# Facec.net
KiCad netlist of a schematic drawn in EAGLE
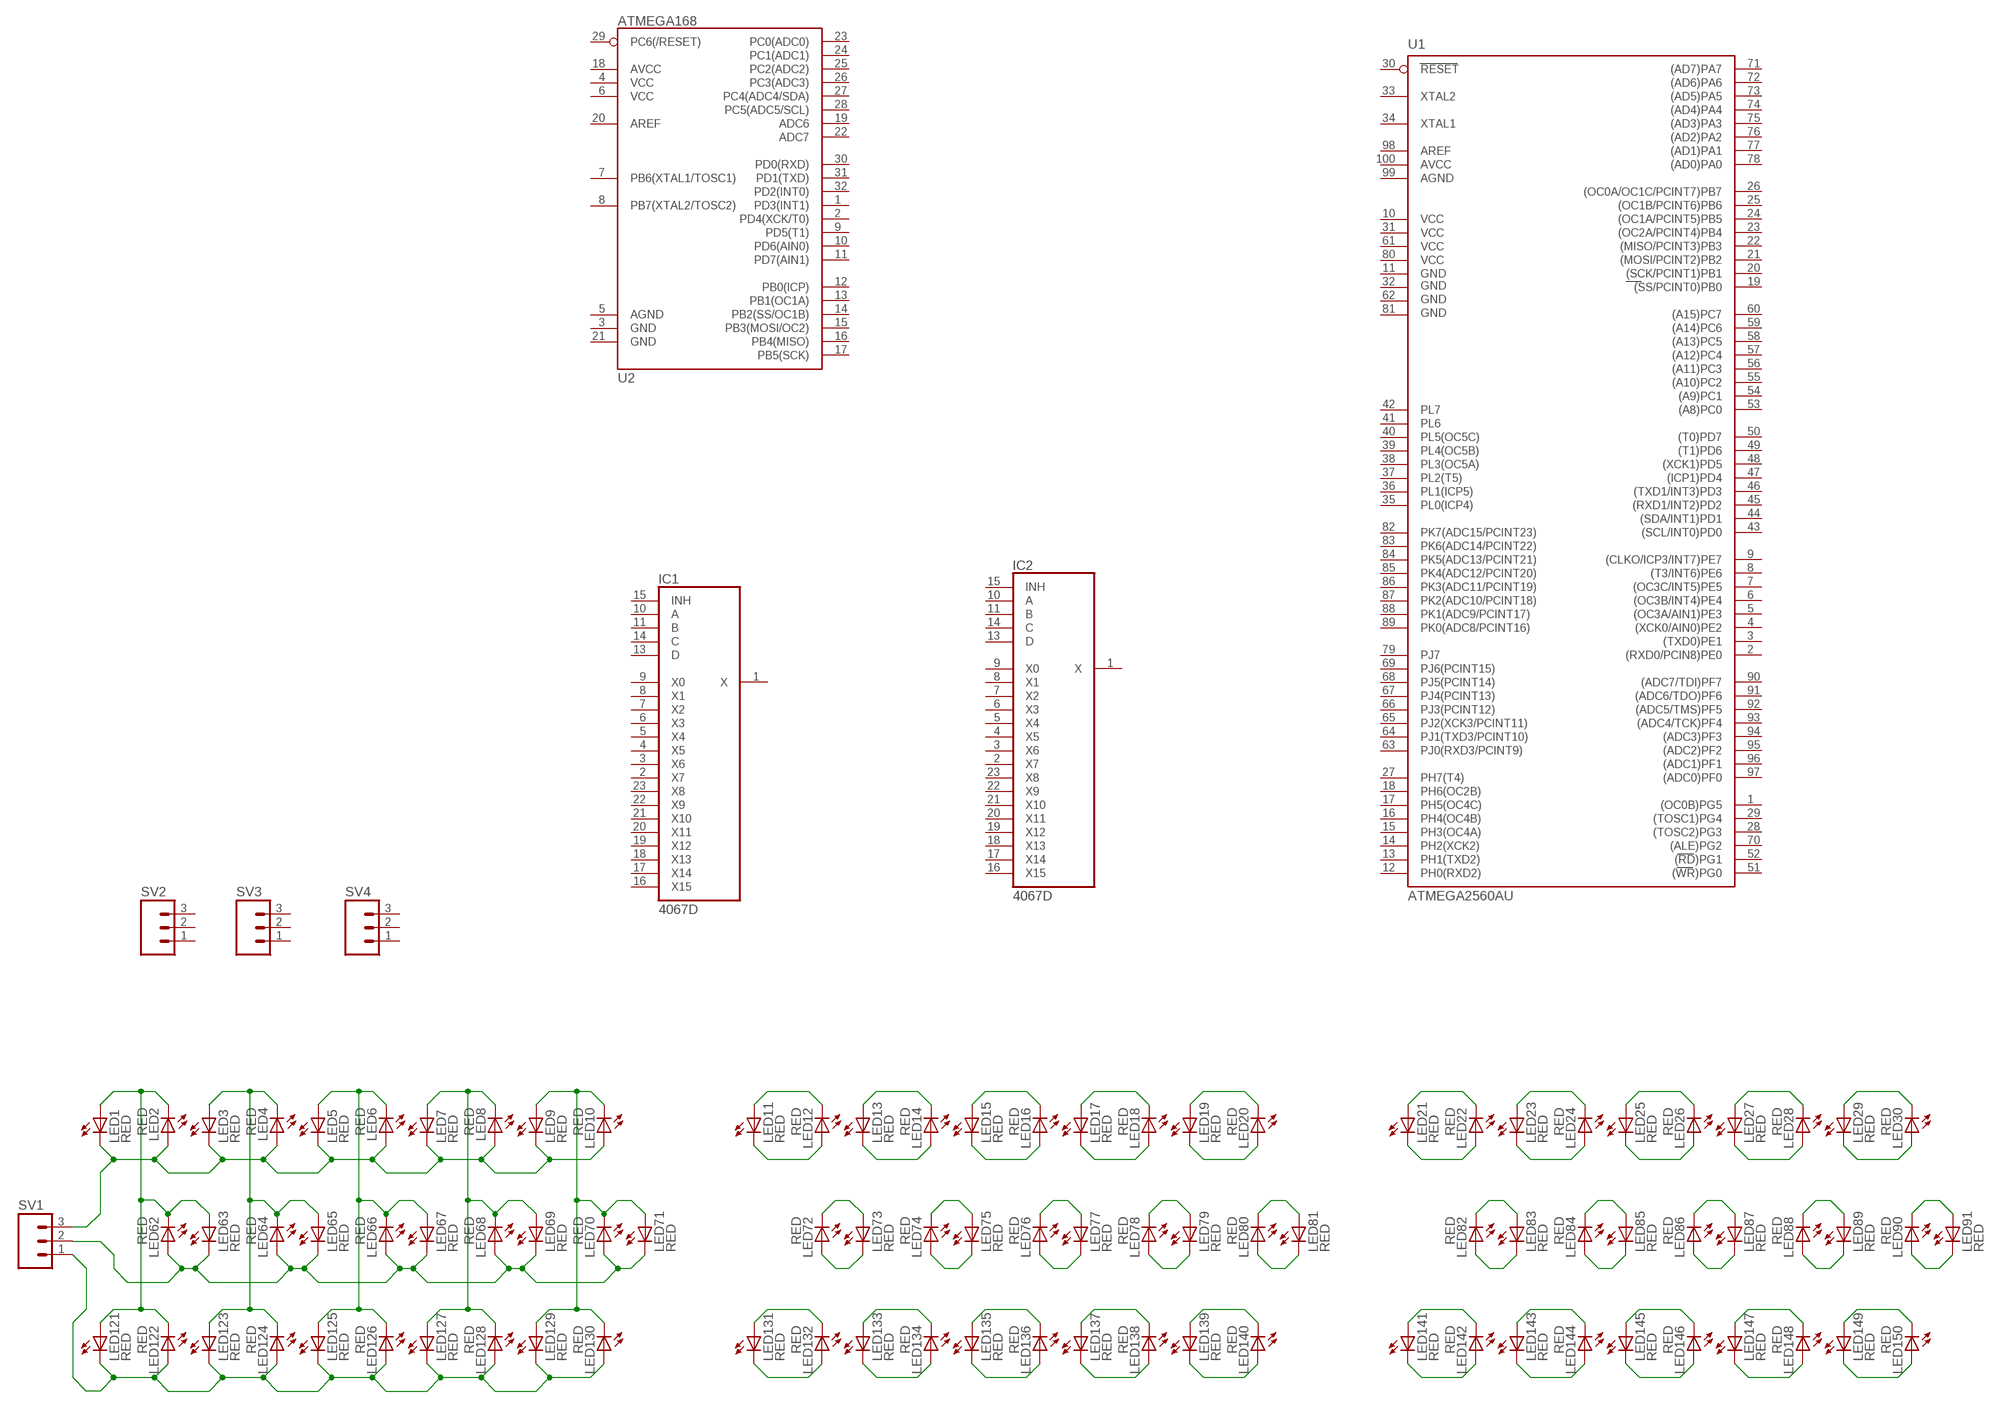
[diagram p0: schematic, sheet 1, part 1 of 2]
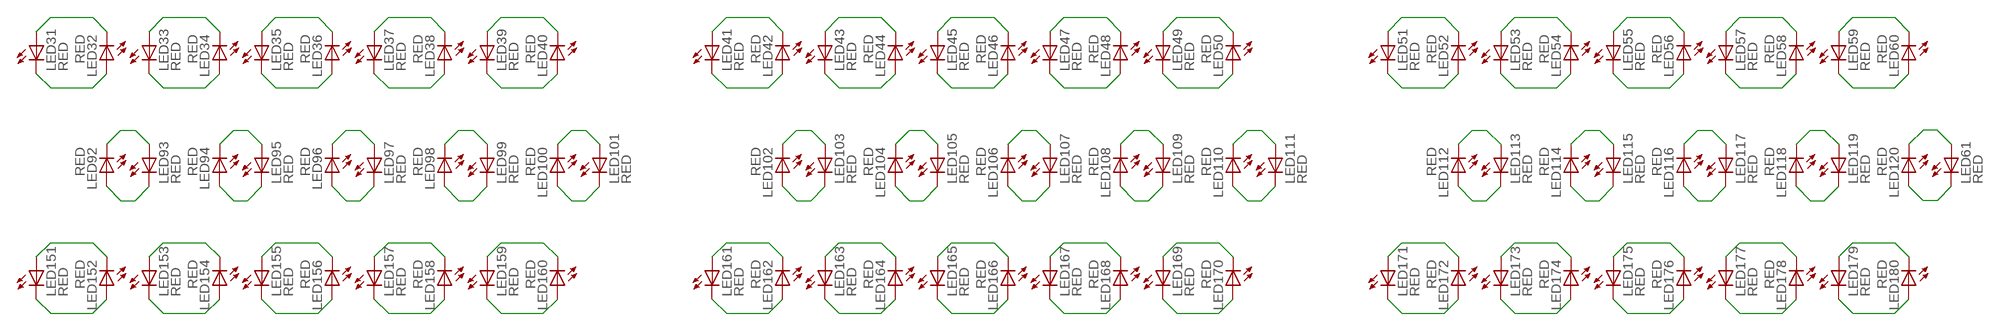
[diagram p1: schematic, sheet 1, part 2 of 2]

(export (version "E")
  (design (tool "Eeschema 10.0.6"))
  (components
    (comp (ref "IC1")
      (value "4067D")
      (footprint "eagle-import:SO24W")
      (libsource (lib "eagle-import") (part "4067D"))
    )
    (comp (ref "IC2")
      (value "4067D")
      (footprint "eagle-import:SO24W")
      (libsource (lib "eagle-import") (part "4067D"))
    )
    (comp (ref "LED1")
      (value "RED")
      (footprint "eagle-import:LED-0603")
      (libsource (lib "eagle-import") (part "LED0603"))
    )
    (comp (ref "LED2")
      (value "RED")
      (footprint "eagle-import:LED-0603")
      (libsource (lib "eagle-import") (part "LED0603"))
    )
    (comp (ref "LED3")
      (value "RED")
      (footprint "eagle-import:LED-0603")
      (libsource (lib "eagle-import") (part "LED0603"))
    )
    (comp (ref "LED4")
      (value "RED")
      (footprint "eagle-import:LED-0603")
      (libsource (lib "eagle-import") (part "LED0603"))
    )
    (comp (ref "LED5")
      (value "RED")
      (footprint "eagle-import:LED-0603")
      (libsource (lib "eagle-import") (part "LED0603"))
    )
    (comp (ref "LED6")
      (value "RED")
      (footprint "eagle-import:LED-0603")
      (libsource (lib "eagle-import") (part "LED0603"))
    )
    (comp (ref "LED7")
      (value "RED")
      (footprint "eagle-import:LED-0603")
      (libsource (lib "eagle-import") (part "LED0603"))
    )
    (comp (ref "LED8")
      (value "RED")
      (footprint "eagle-import:LED-0603")
      (libsource (lib "eagle-import") (part "LED0603"))
    )
    (comp (ref "LED9")
      (value "RED")
      (footprint "eagle-import:LED-0603")
      (libsource (lib "eagle-import") (part "LED0603"))
    )
    (comp (ref "LED10")
      (value "RED")
      (footprint "eagle-import:LED-0603")
      (libsource (lib "eagle-import") (part "LED0603"))
    )
    (comp (ref "LED11")
      (value "RED")
      (footprint "eagle-import:LED-0603")
      (libsource (lib "eagle-import") (part "LED0603"))
    )
    (comp (ref "LED12")
      (value "RED")
      (footprint "eagle-import:LED-0603")
      (libsource (lib "eagle-import") (part "LED0603"))
    )
    (comp (ref "LED13")
      (value "RED")
      (footprint "eagle-import:LED-0603")
      (libsource (lib "eagle-import") (part "LED0603"))
    )
    (comp (ref "LED14")
      (value "RED")
      (footprint "eagle-import:LED-0603")
      (libsource (lib "eagle-import") (part "LED0603"))
    )
    (comp (ref "LED15")
      (value "RED")
      (footprint "eagle-import:LED-0603")
      (libsource (lib "eagle-import") (part "LED0603"))
    )
    (comp (ref "LED16")
      (value "RED")
      (footprint "eagle-import:LED-0603")
      (libsource (lib "eagle-import") (part "LED0603"))
    )
    (comp (ref "LED17")
      (value "RED")
      (footprint "eagle-import:LED-0603")
      (libsource (lib "eagle-import") (part "LED0603"))
    )
    (comp (ref "LED18")
      (value "RED")
      (footprint "eagle-import:LED-0603")
      (libsource (lib "eagle-import") (part "LED0603"))
    )
    (comp (ref "LED19")
      (value "RED")
      (footprint "eagle-import:LED-0603")
      (libsource (lib "eagle-import") (part "LED0603"))
    )
    (comp (ref "LED20")
      (value "RED")
      (footprint "eagle-import:LED-0603")
      (libsource (lib "eagle-import") (part "LED0603"))
    )
    (comp (ref "LED21")
      (value "RED")
      (footprint "eagle-import:LED-0603")
      (libsource (lib "eagle-import") (part "LED0603"))
    )
    (comp (ref "LED22")
      (value "RED")
      (footprint "eagle-import:LED-0603")
      (libsource (lib "eagle-import") (part "LED0603"))
    )
    (comp (ref "LED23")
      (value "RED")
      (footprint "eagle-import:LED-0603")
      (libsource (lib "eagle-import") (part "LED0603"))
    )
    (comp (ref "LED24")
      (value "RED")
      (footprint "eagle-import:LED-0603")
      (libsource (lib "eagle-import") (part "LED0603"))
    )
    (comp (ref "LED25")
      (value "RED")
      (footprint "eagle-import:LED-0603")
      (libsource (lib "eagle-import") (part "LED0603"))
    )
    (comp (ref "LED26")
      (value "RED")
      (footprint "eagle-import:LED-0603")
      (libsource (lib "eagle-import") (part "LED0603"))
    )
    (comp (ref "LED27")
      (value "RED")
      (footprint "eagle-import:LED-0603")
      (libsource (lib "eagle-import") (part "LED0603"))
    )
    (comp (ref "LED28")
      (value "RED")
      (footprint "eagle-import:LED-0603")
      (libsource (lib "eagle-import") (part "LED0603"))
    )
    (comp (ref "LED29")
      (value "RED")
      (footprint "eagle-import:LED-0603")
      (libsource (lib "eagle-import") (part "LED0603"))
    )
    (comp (ref "LED30")
      (value "RED")
      (footprint "eagle-import:LED-0603")
      (libsource (lib "eagle-import") (part "LED0603"))
    )
    (comp (ref "LED31")
      (value "RED")
      (footprint "eagle-import:LED-0603")
      (libsource (lib "eagle-import") (part "LED0603"))
    )
    (comp (ref "LED32")
      (value "RED")
      (footprint "eagle-import:LED-0603")
      (libsource (lib "eagle-import") (part "LED0603"))
    )
    (comp (ref "LED33")
      (value "RED")
      (footprint "eagle-import:LED-0603")
      (libsource (lib "eagle-import") (part "LED0603"))
    )
    (comp (ref "LED34")
      (value "RED")
      (footprint "eagle-import:LED-0603")
      (libsource (lib "eagle-import") (part "LED0603"))
    )
    (comp (ref "LED35")
      (value "RED")
      (footprint "eagle-import:LED-0603")
      (libsource (lib "eagle-import") (part "LED0603"))
    )
    (comp (ref "LED36")
      (value "RED")
      (footprint "eagle-import:LED-0603")
      (libsource (lib "eagle-import") (part "LED0603"))
    )
    (comp (ref "LED37")
      (value "RED")
      (footprint "eagle-import:LED-0603")
      (libsource (lib "eagle-import") (part "LED0603"))
    )
    (comp (ref "LED38")
      (value "RED")
      (footprint "eagle-import:LED-0603")
      (libsource (lib "eagle-import") (part "LED0603"))
    )
    (comp (ref "LED39")
      (value "RED")
      (footprint "eagle-import:LED-0603")
      (libsource (lib "eagle-import") (part "LED0603"))
    )
    (comp (ref "LED40")
      (value "RED")
      (footprint "eagle-import:LED-0603")
      (libsource (lib "eagle-import") (part "LED0603"))
    )
    (comp (ref "LED41")
      (value "RED")
      (footprint "eagle-import:LED-0603")
      (libsource (lib "eagle-import") (part "LED0603"))
    )
    (comp (ref "LED42")
      (value "RED")
      (footprint "eagle-import:LED-0603")
      (libsource (lib "eagle-import") (part "LED0603"))
    )
    (comp (ref "LED43")
      (value "RED")
      (footprint "eagle-import:LED-0603")
      (libsource (lib "eagle-import") (part "LED0603"))
    )
    (comp (ref "LED44")
      (value "RED")
      (footprint "eagle-import:LED-0603")
      (libsource (lib "eagle-import") (part "LED0603"))
    )
    (comp (ref "LED45")
      (value "RED")
      (footprint "eagle-import:LED-0603")
      (libsource (lib "eagle-import") (part "LED0603"))
    )
    (comp (ref "LED46")
      (value "RED")
      (footprint "eagle-import:LED-0603")
      (libsource (lib "eagle-import") (part "LED0603"))
    )
    (comp (ref "LED47")
      (value "RED")
      (footprint "eagle-import:LED-0603")
      (libsource (lib "eagle-import") (part "LED0603"))
    )
    (comp (ref "LED48")
      (value "RED")
      (footprint "eagle-import:LED-0603")
      (libsource (lib "eagle-import") (part "LED0603"))
    )
    (comp (ref "LED49")
      (value "RED")
      (footprint "eagle-import:LED-0603")
      (libsource (lib "eagle-import") (part "LED0603"))
    )
    (comp (ref "LED50")
      (value "RED")
      (footprint "eagle-import:LED-0603")
      (libsource (lib "eagle-import") (part "LED0603"))
    )
    (comp (ref "LED51")
      (value "RED")
      (footprint "eagle-import:LED-0603")
      (libsource (lib "eagle-import") (part "LED0603"))
    )
    (comp (ref "LED52")
      (value "RED")
      (footprint "eagle-import:LED-0603")
      (libsource (lib "eagle-import") (part "LED0603"))
    )
    (comp (ref "LED53")
      (value "RED")
      (footprint "eagle-import:LED-0603")
      (libsource (lib "eagle-import") (part "LED0603"))
    )
    (comp (ref "LED54")
      (value "RED")
      (footprint "eagle-import:LED-0603")
      (libsource (lib "eagle-import") (part "LED0603"))
    )
    (comp (ref "LED55")
      (value "RED")
      (footprint "eagle-import:LED-0603")
      (libsource (lib "eagle-import") (part "LED0603"))
    )
    (comp (ref "LED56")
      (value "RED")
      (footprint "eagle-import:LED-0603")
      (libsource (lib "eagle-import") (part "LED0603"))
    )
    (comp (ref "LED57")
      (value "RED")
      (footprint "eagle-import:LED-0603")
      (libsource (lib "eagle-import") (part "LED0603"))
    )
    (comp (ref "LED58")
      (value "RED")
      (footprint "eagle-import:LED-0603")
      (libsource (lib "eagle-import") (part "LED0603"))
    )
    (comp (ref "LED59")
      (value "RED")
      (footprint "eagle-import:LED-0603")
      (libsource (lib "eagle-import") (part "LED0603"))
    )
    (comp (ref "LED60")
      (value "RED")
      (footprint "eagle-import:LED-0603")
      (libsource (lib "eagle-import") (part "LED0603"))
    )
    (comp (ref "LED61")
      (value "RED")
      (footprint "eagle-import:LED-0603")
      (libsource (lib "eagle-import") (part "LED0603"))
    )
    (comp (ref "LED62")
      (value "RED")
      (footprint "eagle-import:LED-0603")
      (libsource (lib "eagle-import") (part "LED0603"))
    )
    (comp (ref "LED63")
      (value "RED")
      (footprint "eagle-import:LED-0603")
      (libsource (lib "eagle-import") (part "LED0603"))
    )
    (comp (ref "LED64")
      (value "RED")
      (footprint "eagle-import:LED-0603")
      (libsource (lib "eagle-import") (part "LED0603"))
    )
    (comp (ref "LED65")
      (value "RED")
      (footprint "eagle-import:LED-0603")
      (libsource (lib "eagle-import") (part "LED0603"))
    )
    (comp (ref "LED66")
      (value "RED")
      (footprint "eagle-import:LED-0603")
      (libsource (lib "eagle-import") (part "LED0603"))
    )
    (comp (ref "LED67")
      (value "RED")
      (footprint "eagle-import:LED-0603")
      (libsource (lib "eagle-import") (part "LED0603"))
    )
    (comp (ref "LED68")
      (value "RED")
      (footprint "eagle-import:LED-0603")
      (libsource (lib "eagle-import") (part "LED0603"))
    )
    (comp (ref "LED69")
      (value "RED")
      (footprint "eagle-import:LED-0603")
      (libsource (lib "eagle-import") (part "LED0603"))
    )
    (comp (ref "LED70")
      (value "RED")
      (footprint "eagle-import:LED-0603")
      (libsource (lib "eagle-import") (part "LED0603"))
    )
    (comp (ref "LED71")
      (value "RED")
      (footprint "eagle-import:LED-0603")
      (libsource (lib "eagle-import") (part "LED0603"))
    )
    (comp (ref "LED72")
      (value "RED")
      (footprint "eagle-import:LED-0603")
      (libsource (lib "eagle-import") (part "LED0603"))
    )
    (comp (ref "LED73")
      (value "RED")
      (footprint "eagle-import:LED-0603")
      (libsource (lib "eagle-import") (part "LED0603"))
    )
    (comp (ref "LED74")
      (value "RED")
      (footprint "eagle-import:LED-0603")
      (libsource (lib "eagle-import") (part "LED0603"))
    )
    (comp (ref "LED75")
      (value "RED")
      (footprint "eagle-import:LED-0603")
      (libsource (lib "eagle-import") (part "LED0603"))
    )
    (comp (ref "LED76")
      (value "RED")
      (footprint "eagle-import:LED-0603")
      (libsource (lib "eagle-import") (part "LED0603"))
    )
    (comp (ref "LED77")
      (value "RED")
      (footprint "eagle-import:LED-0603")
      (libsource (lib "eagle-import") (part "LED0603"))
    )
    (comp (ref "LED78")
      (value "RED")
      (footprint "eagle-import:LED-0603")
      (libsource (lib "eagle-import") (part "LED0603"))
    )
    (comp (ref "LED79")
      (value "RED")
      (footprint "eagle-import:LED-0603")
      (libsource (lib "eagle-import") (part "LED0603"))
    )
    (comp (ref "LED80")
      (value "RED")
      (footprint "eagle-import:LED-0603")
      (libsource (lib "eagle-import") (part "LED0603"))
    )
    (comp (ref "LED81")
      (value "RED")
      (footprint "eagle-import:LED-0603")
      (libsource (lib "eagle-import") (part "LED0603"))
    )
    (comp (ref "LED82")
      (value "RED")
      (footprint "eagle-import:LED-0603")
      (libsource (lib "eagle-import") (part "LED0603"))
    )
    (comp (ref "LED83")
      (value "RED")
      (footprint "eagle-import:LED-0603")
      (libsource (lib "eagle-import") (part "LED0603"))
    )
    (comp (ref "LED84")
      (value "RED")
      (footprint "eagle-import:LED-0603")
      (libsource (lib "eagle-import") (part "LED0603"))
    )
    (comp (ref "LED85")
      (value "RED")
      (footprint "eagle-import:LED-0603")
      (libsource (lib "eagle-import") (part "LED0603"))
    )
    (comp (ref "LED86")
      (value "RED")
      (footprint "eagle-import:LED-0603")
      (libsource (lib "eagle-import") (part "LED0603"))
    )
    (comp (ref "LED87")
      (value "RED")
      (footprint "eagle-import:LED-0603")
      (libsource (lib "eagle-import") (part "LED0603"))
    )
    (comp (ref "LED88")
      (value "RED")
      (footprint "eagle-import:LED-0603")
      (libsource (lib "eagle-import") (part "LED0603"))
    )
    (comp (ref "LED89")
      (value "RED")
      (footprint "eagle-import:LED-0603")
      (libsource (lib "eagle-import") (part "LED0603"))
    )
    (comp (ref "LED90")
      (value "RED")
      (footprint "eagle-import:LED-0603")
      (libsource (lib "eagle-import") (part "LED0603"))
    )
    (comp (ref "LED91")
      (value "RED")
      (footprint "eagle-import:LED-0603")
      (libsource (lib "eagle-import") (part "LED0603"))
    )
    (comp (ref "LED92")
      (value "RED")
      (footprint "eagle-import:LED-0603")
      (libsource (lib "eagle-import") (part "LED0603"))
    )
    (comp (ref "LED93")
      (value "RED")
      (footprint "eagle-import:LED-0603")
      (libsource (lib "eagle-import") (part "LED0603"))
    )
    (comp (ref "LED94")
      (value "RED")
      (footprint "eagle-import:LED-0603")
      (libsource (lib "eagle-import") (part "LED0603"))
    )
    (comp (ref "LED95")
      (value "RED")
      (footprint "eagle-import:LED-0603")
      (libsource (lib "eagle-import") (part "LED0603"))
    )
    (comp (ref "LED96")
      (value "RED")
      (footprint "eagle-import:LED-0603")
      (libsource (lib "eagle-import") (part "LED0603"))
    )
    (comp (ref "LED97")
      (value "RED")
      (footprint "eagle-import:LED-0603")
      (libsource (lib "eagle-import") (part "LED0603"))
    )
    (comp (ref "LED98")
      (value "RED")
      (footprint "eagle-import:LED-0603")
      (libsource (lib "eagle-import") (part "LED0603"))
    )
    (comp (ref "LED99")
      (value "RED")
      (footprint "eagle-import:LED-0603")
      (libsource (lib "eagle-import") (part "LED0603"))
    )
    (comp (ref "LED100")
      (value "RED")
      (footprint "eagle-import:LED-0603")
      (libsource (lib "eagle-import") (part "LED0603"))
    )
    (comp (ref "LED101")
      (value "RED")
      (footprint "eagle-import:LED-0603")
      (libsource (lib "eagle-import") (part "LED0603"))
    )
    (comp (ref "LED102")
      (value "RED")
      (footprint "eagle-import:LED-0603")
      (libsource (lib "eagle-import") (part "LED0603"))
    )
    (comp (ref "LED103")
      (value "RED")
      (footprint "eagle-import:LED-0603")
      (libsource (lib "eagle-import") (part "LED0603"))
    )
    (comp (ref "LED104")
      (value "RED")
      (footprint "eagle-import:LED-0603")
      (libsource (lib "eagle-import") (part "LED0603"))
    )
    (comp (ref "LED105")
      (value "RED")
      (footprint "eagle-import:LED-0603")
      (libsource (lib "eagle-import") (part "LED0603"))
    )
    (comp (ref "LED106")
      (value "RED")
      (footprint "eagle-import:LED-0603")
      (libsource (lib "eagle-import") (part "LED0603"))
    )
    (comp (ref "LED107")
      (value "RED")
      (footprint "eagle-import:LED-0603")
      (libsource (lib "eagle-import") (part "LED0603"))
    )
    (comp (ref "LED108")
      (value "RED")
      (footprint "eagle-import:LED-0603")
      (libsource (lib "eagle-import") (part "LED0603"))
    )
    (comp (ref "LED109")
      (value "RED")
      (footprint "eagle-import:LED-0603")
      (libsource (lib "eagle-import") (part "LED0603"))
    )
    (comp (ref "LED110")
      (value "RED")
      (footprint "eagle-import:LED-0603")
      (libsource (lib "eagle-import") (part "LED0603"))
    )
    (comp (ref "LED111")
      (value "RED")
      (footprint "eagle-import:LED-0603")
      (libsource (lib "eagle-import") (part "LED0603"))
    )
    (comp (ref "LED112")
      (value "RED")
      (footprint "eagle-import:LED-0603")
      (libsource (lib "eagle-import") (part "LED0603"))
    )
    (comp (ref "LED113")
      (value "RED")
      (footprint "eagle-import:LED-0603")
      (libsource (lib "eagle-import") (part "LED0603"))
    )
    (comp (ref "LED114")
      (value "RED")
      (footprint "eagle-import:LED-0603")
      (libsource (lib "eagle-import") (part "LED0603"))
    )
    (comp (ref "LED115")
      (value "RED")
      (footprint "eagle-import:LED-0603")
      (libsource (lib "eagle-import") (part "LED0603"))
    )
    (comp (ref "LED116")
      (value "RED")
      (footprint "eagle-import:LED-0603")
      (libsource (lib "eagle-import") (part "LED0603"))
    )
    (comp (ref "LED117")
      (value "RED")
      (footprint "eagle-import:LED-0603")
      (libsource (lib "eagle-import") (part "LED0603"))
    )
    (comp (ref "LED118")
      (value "RED")
      (footprint "eagle-import:LED-0603")
      (libsource (lib "eagle-import") (part "LED0603"))
    )
    (comp (ref "LED119")
      (value "RED")
      (footprint "eagle-import:LED-0603")
      (libsource (lib "eagle-import") (part "LED0603"))
    )
    (comp (ref "LED120")
      (value "RED")
      (footprint "eagle-import:LED-0603")
      (libsource (lib "eagle-import") (part "LED0603"))
    )
    (comp (ref "LED121")
      (value "RED")
      (footprint "eagle-import:LED-0603")
      (libsource (lib "eagle-import") (part "LED0603"))
    )
    (comp (ref "LED122")
      (value "RED")
      (footprint "eagle-import:LED-0603")
      (libsource (lib "eagle-import") (part "LED0603"))
    )
    (comp (ref "LED123")
      (value "RED")
      (footprint "eagle-import:LED-0603")
      (libsource (lib "eagle-import") (part "LED0603"))
    )
    (comp (ref "LED124")
      (value "RED")
      (footprint "eagle-import:LED-0603")
      (libsource (lib "eagle-import") (part "LED0603"))
    )
    (comp (ref "LED125")
      (value "RED")
      (footprint "eagle-import:LED-0603")
      (libsource (lib "eagle-import") (part "LED0603"))
    )
    (comp (ref "LED126")
      (value "RED")
      (footprint "eagle-import:LED-0603")
      (libsource (lib "eagle-import") (part "LED0603"))
    )
    (comp (ref "LED127")
      (value "RED")
      (footprint "eagle-import:LED-0603")
      (libsource (lib "eagle-import") (part "LED0603"))
    )
    (comp (ref "LED128")
      (value "RED")
      (footprint "eagle-import:LED-0603")
      (libsource (lib "eagle-import") (part "LED0603"))
    )
    (comp (ref "LED129")
      (value "RED")
      (footprint "eagle-import:LED-0603")
      (libsource (lib "eagle-import") (part "LED0603"))
    )
    (comp (ref "LED130")
      (value "RED")
      (footprint "eagle-import:LED-0603")
      (libsource (lib "eagle-import") (part "LED0603"))
    )
    (comp (ref "LED131")
      (value "RED")
      (footprint "eagle-import:LED-0603")
      (libsource (lib "eagle-import") (part "LED0603"))
    )
    (comp (ref "LED132")
      (value "RED")
      (footprint "eagle-import:LED-0603")
      (libsource (lib "eagle-import") (part "LED0603"))
    )
    (comp (ref "LED133")
      (value "RED")
      (footprint "eagle-import:LED-0603")
      (libsource (lib "eagle-import") (part "LED0603"))
    )
    (comp (ref "LED134")
      (value "RED")
      (footprint "eagle-import:LED-0603")
      (libsource (lib "eagle-import") (part "LED0603"))
    )
    (comp (ref "LED135")
      (value "RED")
      (footprint "eagle-import:LED-0603")
      (libsource (lib "eagle-import") (part "LED0603"))
    )
    (comp (ref "LED136")
      (value "RED")
      (footprint "eagle-import:LED-0603")
      (libsource (lib "eagle-import") (part "LED0603"))
    )
    (comp (ref "LED137")
      (value "RED")
      (footprint "eagle-import:LED-0603")
      (libsource (lib "eagle-import") (part "LED0603"))
    )
    (comp (ref "LED138")
      (value "RED")
      (footprint "eagle-import:LED-0603")
      (libsource (lib "eagle-import") (part "LED0603"))
    )
    (comp (ref "LED139")
      (value "RED")
      (footprint "eagle-import:LED-0603")
      (libsource (lib "eagle-import") (part "LED0603"))
    )
    (comp (ref "LED140")
      (value "RED")
      (footprint "eagle-import:LED-0603")
      (libsource (lib "eagle-import") (part "LED0603"))
    )
    (comp (ref "LED141")
      (value "RED")
      (footprint "eagle-import:LED-0603")
      (libsource (lib "eagle-import") (part "LED0603"))
    )
    (comp (ref "LED142")
      (value "RED")
      (footprint "eagle-import:LED-0603")
      (libsource (lib "eagle-import") (part "LED0603"))
    )
    (comp (ref "LED143")
      (value "RED")
      (footprint "eagle-import:LED-0603")
      (libsource (lib "eagle-import") (part "LED0603"))
    )
    (comp (ref "LED144")
      (value "RED")
      (footprint "eagle-import:LED-0603")
      (libsource (lib "eagle-import") (part "LED0603"))
    )
    (comp (ref "LED145")
      (value "RED")
      (footprint "eagle-import:LED-0603")
      (libsource (lib "eagle-import") (part "LED0603"))
    )
    (comp (ref "LED146")
      (value "RED")
      (footprint "eagle-import:LED-0603")
      (libsource (lib "eagle-import") (part "LED0603"))
    )
    (comp (ref "LED147")
      (value "RED")
      (footprint "eagle-import:LED-0603")
      (libsource (lib "eagle-import") (part "LED0603"))
    )
    (comp (ref "LED148")
      (value "RED")
      (footprint "eagle-import:LED-0603")
      (libsource (lib "eagle-import") (part "LED0603"))
    )
    (comp (ref "LED149")
      (value "RED")
      (footprint "eagle-import:LED-0603")
      (libsource (lib "eagle-import") (part "LED0603"))
    )
    (comp (ref "LED150")
      (value "RED")
      (footprint "eagle-import:LED-0603")
      (libsource (lib "eagle-import") (part "LED0603"))
    )
    (comp (ref "LED151")
      (value "RED")
      (footprint "eagle-import:LED-0603")
      (libsource (lib "eagle-import") (part "LED0603"))
    )
    (comp (ref "LED152")
      (value "RED")
      (footprint "eagle-import:LED-0603")
      (libsource (lib "eagle-import") (part "LED0603"))
    )
    (comp (ref "LED153")
      (value "RED")
      (footprint "eagle-import:LED-0603")
      (libsource (lib "eagle-import") (part "LED0603"))
    )
    (comp (ref "LED154")
      (value "RED")
      (footprint "eagle-import:LED-0603")
      (libsource (lib "eagle-import") (part "LED0603"))
    )
    (comp (ref "LED155")
      (value "RED")
      (footprint "eagle-import:LED-0603")
      (libsource (lib "eagle-import") (part "LED0603"))
    )
    (comp (ref "LED156")
      (value "RED")
      (footprint "eagle-import:LED-0603")
      (libsource (lib "eagle-import") (part "LED0603"))
    )
    (comp (ref "LED157")
      (value "RED")
      (footprint "eagle-import:LED-0603")
      (libsource (lib "eagle-import") (part "LED0603"))
    )
    (comp (ref "LED158")
      (value "RED")
      (footprint "eagle-import:LED-0603")
      (libsource (lib "eagle-import") (part "LED0603"))
    )
    (comp (ref "LED159")
      (value "RED")
      (footprint "eagle-import:LED-0603")
      (libsource (lib "eagle-import") (part "LED0603"))
    )
    (comp (ref "LED160")
      (value "RED")
      (footprint "eagle-import:LED-0603")
      (libsource (lib "eagle-import") (part "LED0603"))
    )
    (comp (ref "LED161")
      (value "RED")
      (footprint "eagle-import:LED-0603")
      (libsource (lib "eagle-import") (part "LED0603"))
    )
    (comp (ref "LED162")
      (value "RED")
      (footprint "eagle-import:LED-0603")
      (libsource (lib "eagle-import") (part "LED0603"))
    )
    (comp (ref "LED163")
      (value "RED")
      (footprint "eagle-import:LED-0603")
      (libsource (lib "eagle-import") (part "LED0603"))
    )
    (comp (ref "LED164")
      (value "RED")
      (footprint "eagle-import:LED-0603")
      (libsource (lib "eagle-import") (part "LED0603"))
    )
    (comp (ref "LED165")
      (value "RED")
      (footprint "eagle-import:LED-0603")
      (libsource (lib "eagle-import") (part "LED0603"))
    )
    (comp (ref "LED166")
      (value "RED")
      (footprint "eagle-import:LED-0603")
      (libsource (lib "eagle-import") (part "LED0603"))
    )
    (comp (ref "LED167")
      (value "RED")
      (footprint "eagle-import:LED-0603")
      (libsource (lib "eagle-import") (part "LED0603"))
    )
    (comp (ref "LED168")
      (value "RED")
      (footprint "eagle-import:LED-0603")
      (libsource (lib "eagle-import") (part "LED0603"))
    )
    (comp (ref "LED169")
      (value "RED")
      (footprint "eagle-import:LED-0603")
      (libsource (lib "eagle-import") (part "LED0603"))
    )
    (comp (ref "LED170")
      (value "RED")
      (footprint "eagle-import:LED-0603")
      (libsource (lib "eagle-import") (part "LED0603"))
    )
    (comp (ref "LED171")
      (value "RED")
      (footprint "eagle-import:LED-0603")
      (libsource (lib "eagle-import") (part "LED0603"))
    )
    (comp (ref "LED172")
      (value "RED")
      (footprint "eagle-import:LED-0603")
      (libsource (lib "eagle-import") (part "LED0603"))
    )
    (comp (ref "LED173")
      (value "RED")
      (footprint "eagle-import:LED-0603")
      (libsource (lib "eagle-import") (part "LED0603"))
    )
    (comp (ref "LED174")
      (value "RED")
      (footprint "eagle-import:LED-0603")
      (libsource (lib "eagle-import") (part "LED0603"))
    )
    (comp (ref "LED175")
      (value "RED")
      (footprint "eagle-import:LED-0603")
      (libsource (lib "eagle-import") (part "LED0603"))
    )
    (comp (ref "LED176")
      (value "RED")
      (footprint "eagle-import:LED-0603")
      (libsource (lib "eagle-import") (part "LED0603"))
    )
    (comp (ref "LED177")
      (value "RED")
      (footprint "eagle-import:LED-0603")
      (libsource (lib "eagle-import") (part "LED0603"))
    )
    (comp (ref "LED178")
      (value "RED")
      (footprint "eagle-import:LED-0603")
      (libsource (lib "eagle-import") (part "LED0603"))
    )
    (comp (ref "LED179")
      (value "RED")
      (footprint "eagle-import:LED-0603")
      (libsource (lib "eagle-import") (part "LED0603"))
    )
    (comp (ref "LED180")
      (value "RED")
      (footprint "eagle-import:LED-0603")
      (libsource (lib "eagle-import") (part "LED0603"))
    )
    (comp (ref "SV1")
      (value "M03PTH")
      (footprint "eagle-import:1X03")
      (libsource (lib "eagle-import") (part "M03PTH"))
    )
    (comp (ref "SV2")
      (value "M03PTH")
      (footprint "eagle-import:1X03")
      (libsource (lib "eagle-import") (part "M03PTH"))
    )
    (comp (ref "SV3")
      (value "M03PTH")
      (footprint "eagle-import:1X03")
      (libsource (lib "eagle-import") (part "M03PTH"))
    )
    (comp (ref "SV4")
      (value "M03PTH")
      (footprint "eagle-import:1X03")
      (libsource (lib "eagle-import") (part "M03PTH"))
    )
    (comp (ref "U1")
      (value "ATMEGA2560AU")
      (footprint "eagle-import:TQFP100")
      (libsource (lib "eagle-import") (part "ATMEGA2560AU"))
    )
    (comp (ref "U2")
      (value "ATMEGA168")
      (footprint "eagle-import:TQFP32-08")
      (libsource (lib "eagle-import") (part "ATMEGA168"))
    )
  )
  (nets
    (net (code "1") (name "/AGND") (class "Default")
      (node (ref "U1") (pin "99") (pinfunction "AGND_99") (pintype "power_in"))
    )
    (net (code "2") (name "/AVCC") (class "Default")
      (node (ref "U1") (pin "100") (pinfunction "AVCC_100") (pintype "power_in"))
    )
    (net (code "3") (name "/GND") (class "Default")
      (node (ref "U1") (pin "11") (pinfunction "GND_11") (pintype "power_in"))
    )
    (net (code "4") (name "/GND1") (class "Default")
      (node (ref "U1") (pin "32") (pinfunction "GND1_32") (pintype "power_in"))
    )
    (net (code "5") (name "/GND2") (class "Default")
      (node (ref "U1") (pin "62") (pinfunction "GND2_62") (pintype "power_in"))
    )
    (net (code "6") (name "/GND3") (class "Default")
      (node (ref "U1") (pin "81") (pinfunction "GND3_81") (pintype "power_in"))
    )
    (net (code "7") (name "/VCC") (class "Default")
      (node (ref "U1") (pin "10") (pinfunction "VCC_10") (pintype "power_in"))
    )
    (net (code "8") (name "/VCC1") (class "Default")
      (node (ref "U1") (pin "31") (pinfunction "VCC1_31") (pintype "power_in"))
    )
    (net (code "9") (name "/VCC2") (class "Default")
      (node (ref "U1") (pin "61") (pinfunction "VCC2_61") (pintype "power_in"))
    )
    (net (code "10") (name "/VCC3") (class "Default")
      (node (ref "U1") (pin "80") (pinfunction "VCC3_80") (pintype "power_in"))
    )
    (net (code "11") (name "Net-(LED1-PadA)") (class "Default")
      (node (ref "LED1") (pin "A") (pinfunction "A_A") (pintype "passive"))
      (node (ref "LED121") (pin "A") (pinfunction "A_A") (pintype "passive"))
      (node (ref "LED122") (pin "C") (pinfunction "C_C") (pintype "passive"))
      (node (ref "LED2") (pin "C") (pinfunction "C_C") (pintype "passive"))
      (node (ref "LED62") (pin "C") (pinfunction "C_C") (pintype "passive"))
      (node (ref "LED63") (pin "A") (pinfunction "A_A") (pintype "passive"))
    )
    (net (code "12") (name "Net-(LED1-PadC)") (class "Default")
      (node (ref "LED1") (pin "C") (pinfunction "C_C") (pintype "passive"))
      (node (ref "LED10") (pin "A") (pinfunction "A_A") (pintype "passive"))
      (node (ref "LED2") (pin "A") (pinfunction "A_A") (pintype "passive"))
      (node (ref "LED3") (pin "C") (pinfunction "C_C") (pintype "passive"))
      (node (ref "LED4") (pin "A") (pinfunction "A_A") (pintype "passive"))
      (node (ref "LED5") (pin "C") (pinfunction "C_C") (pintype "passive"))
      (node (ref "LED6") (pin "A") (pinfunction "A_A") (pintype "passive"))
      (node (ref "LED7") (pin "C") (pinfunction "C_C") (pintype "passive"))
      (node (ref "LED8") (pin "A") (pinfunction "A_A") (pintype "passive"))
      (node (ref "LED9") (pin "C") (pinfunction "C_C") (pintype "passive"))
      (node (ref "SV1") (pin "3") (pinfunction "3_3") (pintype "passive"))
    )
    (net (code "13") (name "Net-(LED10-PadC)") (class "Default")
      (node (ref "LED10") (pin "C") (pinfunction "C_C") (pintype "passive"))
      (node (ref "LED129") (pin "A") (pinfunction "A_A") (pintype "passive"))
      (node (ref "LED130") (pin "C") (pinfunction "C_C") (pintype "passive"))
      (node (ref "LED70") (pin "C") (pinfunction "C_C") (pintype "passive"))
      (node (ref "LED71") (pin "A") (pinfunction "A_A") (pintype "passive"))
      (node (ref "LED9") (pin "A") (pinfunction "A_A") (pintype "passive"))
    )
    (net (code "14") (name "Net-(LED11-PadA)") (class "Default")
      (node (ref "LED11") (pin "A") (pinfunction "A_A") (pintype "passive"))
      (node (ref "LED12") (pin "C") (pinfunction "C_C") (pintype "passive"))
    )
    (net (code "15") (name "Net-(LED11-PadC)") (class "Default")
      (node (ref "LED11") (pin "C") (pinfunction "C_C") (pintype "passive"))
      (node (ref "LED12") (pin "A") (pinfunction "A_A") (pintype "passive"))
    )
    (net (code "16") (name "Net-(LED13-PadA)") (class "Default")
      (node (ref "LED13") (pin "A") (pinfunction "A_A") (pintype "passive"))
      (node (ref "LED14") (pin "C") (pinfunction "C_C") (pintype "passive"))
    )
    (net (code "17") (name "Net-(LED13-PadC)") (class "Default")
      (node (ref "LED13") (pin "C") (pinfunction "C_C") (pintype "passive"))
      (node (ref "LED14") (pin "A") (pinfunction "A_A") (pintype "passive"))
    )
    (net (code "18") (name "Net-(LED15-PadA)") (class "Default")
      (node (ref "LED15") (pin "A") (pinfunction "A_A") (pintype "passive"))
      (node (ref "LED16") (pin "C") (pinfunction "C_C") (pintype "passive"))
    )
    (net (code "19") (name "Net-(LED15-PadC)") (class "Default")
      (node (ref "LED15") (pin "C") (pinfunction "C_C") (pintype "passive"))
      (node (ref "LED16") (pin "A") (pinfunction "A_A") (pintype "passive"))
    )
    (net (code "20") (name "Net-(LED17-PadA)") (class "Default")
      (node (ref "LED17") (pin "A") (pinfunction "A_A") (pintype "passive"))
      (node (ref "LED18") (pin "C") (pinfunction "C_C") (pintype "passive"))
    )
    (net (code "21") (name "Net-(LED17-PadC)") (class "Default")
      (node (ref "LED17") (pin "C") (pinfunction "C_C") (pintype "passive"))
      (node (ref "LED18") (pin "A") (pinfunction "A_A") (pintype "passive"))
    )
    (net (code "22") (name "Net-(LED19-PadA)") (class "Default")
      (node (ref "LED19") (pin "A") (pinfunction "A_A") (pintype "passive"))
      (node (ref "LED20") (pin "C") (pinfunction "C_C") (pintype "passive"))
    )
    (net (code "23") (name "Net-(LED19-PadC)") (class "Default")
      (node (ref "LED19") (pin "C") (pinfunction "C_C") (pintype "passive"))
      (node (ref "LED20") (pin "A") (pinfunction "A_A") (pintype "passive"))
    )
    (net (code "24") (name "Net-(LED21-PadA)") (class "Default")
      (node (ref "LED21") (pin "A") (pinfunction "A_A") (pintype "passive"))
      (node (ref "LED22") (pin "C") (pinfunction "C_C") (pintype "passive"))
    )
    (net (code "25") (name "Net-(LED21-PadC)") (class "Default")
      (node (ref "LED21") (pin "C") (pinfunction "C_C") (pintype "passive"))
      (node (ref "LED22") (pin "A") (pinfunction "A_A") (pintype "passive"))
    )
    (net (code "26") (name "Net-(LED23-PadA)") (class "Default")
      (node (ref "LED23") (pin "A") (pinfunction "A_A") (pintype "passive"))
      (node (ref "LED24") (pin "C") (pinfunction "C_C") (pintype "passive"))
    )
    (net (code "27") (name "Net-(LED23-PadC)") (class "Default")
      (node (ref "LED23") (pin "C") (pinfunction "C_C") (pintype "passive"))
      (node (ref "LED24") (pin "A") (pinfunction "A_A") (pintype "passive"))
    )
    (net (code "28") (name "Net-(LED25-PadA)") (class "Default")
      (node (ref "LED25") (pin "A") (pinfunction "A_A") (pintype "passive"))
      (node (ref "LED26") (pin "C") (pinfunction "C_C") (pintype "passive"))
    )
    (net (code "29") (name "Net-(LED25-PadC)") (class "Default")
      (node (ref "LED25") (pin "C") (pinfunction "C_C") (pintype "passive"))
      (node (ref "LED26") (pin "A") (pinfunction "A_A") (pintype "passive"))
    )
    (net (code "30") (name "Net-(LED27-PadA)") (class "Default")
      (node (ref "LED27") (pin "A") (pinfunction "A_A") (pintype "passive"))
      (node (ref "LED28") (pin "C") (pinfunction "C_C") (pintype "passive"))
    )
    (net (code "31") (name "Net-(LED27-PadC)") (class "Default")
      (node (ref "LED27") (pin "C") (pinfunction "C_C") (pintype "passive"))
      (node (ref "LED28") (pin "A") (pinfunction "A_A") (pintype "passive"))
    )
    (net (code "32") (name "Net-(LED29-PadA)") (class "Default")
      (node (ref "LED29") (pin "A") (pinfunction "A_A") (pintype "passive"))
      (node (ref "LED30") (pin "C") (pinfunction "C_C") (pintype "passive"))
    )
    (net (code "33") (name "Net-(LED29-PadC)") (class "Default")
      (node (ref "LED29") (pin "C") (pinfunction "C_C") (pintype "passive"))
      (node (ref "LED30") (pin "A") (pinfunction "A_A") (pintype "passive"))
    )
    (net (code "34") (name "Net-(LED31-PadA)") (class "Default")
      (node (ref "LED31") (pin "A") (pinfunction "A_A") (pintype "passive"))
      (node (ref "LED32") (pin "C") (pinfunction "C_C") (pintype "passive"))
    )
    (net (code "35") (name "Net-(LED31-PadC)") (class "Default")
      (node (ref "LED31") (pin "C") (pinfunction "C_C") (pintype "passive"))
      (node (ref "LED32") (pin "A") (pinfunction "A_A") (pintype "passive"))
    )
    (net (code "36") (name "Net-(LED33-PadA)") (class "Default")
      (node (ref "LED33") (pin "A") (pinfunction "A_A") (pintype "passive"))
      (node (ref "LED34") (pin "C") (pinfunction "C_C") (pintype "passive"))
    )
    (net (code "37") (name "Net-(LED33-PadC)") (class "Default")
      (node (ref "LED33") (pin "C") (pinfunction "C_C") (pintype "passive"))
      (node (ref "LED34") (pin "A") (pinfunction "A_A") (pintype "passive"))
    )
    (net (code "38") (name "Net-(LED35-PadA)") (class "Default")
      (node (ref "LED35") (pin "A") (pinfunction "A_A") (pintype "passive"))
      (node (ref "LED36") (pin "C") (pinfunction "C_C") (pintype "passive"))
    )
    (net (code "39") (name "Net-(LED35-PadC)") (class "Default")
      (node (ref "LED35") (pin "C") (pinfunction "C_C") (pintype "passive"))
      (node (ref "LED36") (pin "A") (pinfunction "A_A") (pintype "passive"))
    )
    (net (code "40") (name "Net-(LED37-PadA)") (class "Default")
      (node (ref "LED37") (pin "A") (pinfunction "A_A") (pintype "passive"))
      (node (ref "LED38") (pin "C") (pinfunction "C_C") (pintype "passive"))
    )
    (net (code "41") (name "Net-(LED37-PadC)") (class "Default")
      (node (ref "LED37") (pin "C") (pinfunction "C_C") (pintype "passive"))
      (node (ref "LED38") (pin "A") (pinfunction "A_A") (pintype "passive"))
    )
    (net (code "42") (name "Net-(LED39-PadA)") (class "Default")
      (node (ref "LED39") (pin "A") (pinfunction "A_A") (pintype "passive"))
      (node (ref "LED40") (pin "C") (pinfunction "C_C") (pintype "passive"))
    )
    (net (code "43") (name "Net-(LED39-PadC)") (class "Default")
      (node (ref "LED39") (pin "C") (pinfunction "C_C") (pintype "passive"))
      (node (ref "LED40") (pin "A") (pinfunction "A_A") (pintype "passive"))
    )
    (net (code "44") (name "Net-(LED41-PadA)") (class "Default")
      (node (ref "LED41") (pin "A") (pinfunction "A_A") (pintype "passive"))
      (node (ref "LED42") (pin "C") (pinfunction "C_C") (pintype "passive"))
    )
    (net (code "45") (name "Net-(LED41-PadC)") (class "Default")
      (node (ref "LED41") (pin "C") (pinfunction "C_C") (pintype "passive"))
      (node (ref "LED42") (pin "A") (pinfunction "A_A") (pintype "passive"))
    )
    (net (code "46") (name "Net-(LED43-PadA)") (class "Default")
      (node (ref "LED43") (pin "A") (pinfunction "A_A") (pintype "passive"))
      (node (ref "LED44") (pin "C") (pinfunction "C_C") (pintype "passive"))
    )
    (net (code "47") (name "Net-(LED43-PadC)") (class "Default")
      (node (ref "LED43") (pin "C") (pinfunction "C_C") (pintype "passive"))
      (node (ref "LED44") (pin "A") (pinfunction "A_A") (pintype "passive"))
    )
    (net (code "48") (name "Net-(LED45-PadA)") (class "Default")
      (node (ref "LED45") (pin "A") (pinfunction "A_A") (pintype "passive"))
      (node (ref "LED46") (pin "C") (pinfunction "C_C") (pintype "passive"))
    )
    (net (code "49") (name "Net-(LED45-PadC)") (class "Default")
      (node (ref "LED45") (pin "C") (pinfunction "C_C") (pintype "passive"))
      (node (ref "LED46") (pin "A") (pinfunction "A_A") (pintype "passive"))
    )
    (net (code "50") (name "Net-(LED47-PadA)") (class "Default")
      (node (ref "LED47") (pin "A") (pinfunction "A_A") (pintype "passive"))
      (node (ref "LED48") (pin "C") (pinfunction "C_C") (pintype "passive"))
    )
    (net (code "51") (name "Net-(LED47-PadC)") (class "Default")
      (node (ref "LED47") (pin "C") (pinfunction "C_C") (pintype "passive"))
      (node (ref "LED48") (pin "A") (pinfunction "A_A") (pintype "passive"))
    )
    (net (code "52") (name "Net-(LED49-PadA)") (class "Default")
      (node (ref "LED49") (pin "A") (pinfunction "A_A") (pintype "passive"))
      (node (ref "LED50") (pin "C") (pinfunction "C_C") (pintype "passive"))
    )
    (net (code "53") (name "Net-(LED49-PadC)") (class "Default")
      (node (ref "LED49") (pin "C") (pinfunction "C_C") (pintype "passive"))
      (node (ref "LED50") (pin "A") (pinfunction "A_A") (pintype "passive"))
    )
    (net (code "54") (name "Net-(LED51-PadA)") (class "Default")
      (node (ref "LED51") (pin "A") (pinfunction "A_A") (pintype "passive"))
      (node (ref "LED52") (pin "C") (pinfunction "C_C") (pintype "passive"))
    )
    (net (code "55") (name "Net-(LED51-PadC)") (class "Default")
      (node (ref "LED51") (pin "C") (pinfunction "C_C") (pintype "passive"))
      (node (ref "LED52") (pin "A") (pinfunction "A_A") (pintype "passive"))
    )
    (net (code "56") (name "Net-(LED53-PadA)") (class "Default")
      (node (ref "LED53") (pin "A") (pinfunction "A_A") (pintype "passive"))
      (node (ref "LED54") (pin "C") (pinfunction "C_C") (pintype "passive"))
    )
    (net (code "57") (name "Net-(LED53-PadC)") (class "Default")
      (node (ref "LED53") (pin "C") (pinfunction "C_C") (pintype "passive"))
      (node (ref "LED54") (pin "A") (pinfunction "A_A") (pintype "passive"))
    )
    (net (code "58") (name "Net-(LED55-PadA)") (class "Default")
      (node (ref "LED55") (pin "A") (pinfunction "A_A") (pintype "passive"))
      (node (ref "LED56") (pin "C") (pinfunction "C_C") (pintype "passive"))
    )
    (net (code "59") (name "Net-(LED55-PadC)") (class "Default")
      (node (ref "LED55") (pin "C") (pinfunction "C_C") (pintype "passive"))
      (node (ref "LED56") (pin "A") (pinfunction "A_A") (pintype "passive"))
    )
    (net (code "60") (name "Net-(LED57-PadA)") (class "Default")
      (node (ref "LED57") (pin "A") (pinfunction "A_A") (pintype "passive"))
      (node (ref "LED58") (pin "C") (pinfunction "C_C") (pintype "passive"))
    )
    (net (code "61") (name "Net-(LED57-PadC)") (class "Default")
      (node (ref "LED57") (pin "C") (pinfunction "C_C") (pintype "passive"))
      (node (ref "LED58") (pin "A") (pinfunction "A_A") (pintype "passive"))
    )
    (net (code "62") (name "Net-(LED59-PadA)") (class "Default")
      (node (ref "LED59") (pin "A") (pinfunction "A_A") (pintype "passive"))
      (node (ref "LED60") (pin "C") (pinfunction "C_C") (pintype "passive"))
    )
    (net (code "63") (name "Net-(LED59-PadC)") (class "Default")
      (node (ref "LED59") (pin "C") (pinfunction "C_C") (pintype "passive"))
      (node (ref "LED60") (pin "A") (pinfunction "A_A") (pintype "passive"))
    )
    (net (code "64") (name "Net-(LED62-PadA)") (class "Default")
      (node (ref "LED62") (pin "A") (pinfunction "A_A") (pintype "passive"))
      (node (ref "LED63") (pin "C") (pinfunction "C_C") (pintype "passive"))
      (node (ref "LED64") (pin "A") (pinfunction "A_A") (pintype "passive"))
      (node (ref "LED65") (pin "C") (pinfunction "C_C") (pintype "passive"))
      (node (ref "LED66") (pin "A") (pinfunction "A_A") (pintype "passive"))
      (node (ref "LED67") (pin "C") (pinfunction "C_C") (pintype "passive"))
      (node (ref "LED68") (pin "A") (pinfunction "A_A") (pintype "passive"))
      (node (ref "LED69") (pin "C") (pinfunction "C_C") (pintype "passive"))
      (node (ref "LED70") (pin "A") (pinfunction "A_A") (pintype "passive"))
      (node (ref "LED71") (pin "C") (pinfunction "C_C") (pintype "passive"))
      (node (ref "SV1") (pin "2") (pinfunction "2_2") (pintype "passive"))
    )
    (net (code "65") (name "Net-(LED72-PadA)") (class "Default")
      (node (ref "LED72") (pin "A") (pinfunction "A_A") (pintype "passive"))
      (node (ref "LED73") (pin "C") (pinfunction "C_C") (pintype "passive"))
    )
    (net (code "66") (name "Net-(LED72-PadC)") (class "Default")
      (node (ref "LED72") (pin "C") (pinfunction "C_C") (pintype "passive"))
      (node (ref "LED73") (pin "A") (pinfunction "A_A") (pintype "passive"))
    )
    (net (code "67") (name "Net-(LED74-PadA)") (class "Default")
      (node (ref "LED74") (pin "A") (pinfunction "A_A") (pintype "passive"))
      (node (ref "LED75") (pin "C") (pinfunction "C_C") (pintype "passive"))
    )
    (net (code "68") (name "Net-(LED74-PadC)") (class "Default")
      (node (ref "LED74") (pin "C") (pinfunction "C_C") (pintype "passive"))
      (node (ref "LED75") (pin "A") (pinfunction "A_A") (pintype "passive"))
    )
    (net (code "69") (name "Net-(LED76-PadA)") (class "Default")
      (node (ref "LED76") (pin "A") (pinfunction "A_A") (pintype "passive"))
      (node (ref "LED77") (pin "C") (pinfunction "C_C") (pintype "passive"))
    )
    (net (code "70") (name "Net-(LED76-PadC)") (class "Default")
      (node (ref "LED76") (pin "C") (pinfunction "C_C") (pintype "passive"))
      (node (ref "LED77") (pin "A") (pinfunction "A_A") (pintype "passive"))
    )
    (net (code "71") (name "Net-(LED78-PadA)") (class "Default")
      (node (ref "LED78") (pin "A") (pinfunction "A_A") (pintype "passive"))
      (node (ref "LED79") (pin "C") (pinfunction "C_C") (pintype "passive"))
    )
    (net (code "72") (name "Net-(LED78-PadC)") (class "Default")
      (node (ref "LED78") (pin "C") (pinfunction "C_C") (pintype "passive"))
      (node (ref "LED79") (pin "A") (pinfunction "A_A") (pintype "passive"))
    )
    (net (code "73") (name "Net-(LED80-PadA)") (class "Default")
      (node (ref "LED80") (pin "A") (pinfunction "A_A") (pintype "passive"))
      (node (ref "LED81") (pin "C") (pinfunction "C_C") (pintype "passive"))
    )
    (net (code "74") (name "Net-(LED80-PadC)") (class "Default")
      (node (ref "LED80") (pin "C") (pinfunction "C_C") (pintype "passive"))
      (node (ref "LED81") (pin "A") (pinfunction "A_A") (pintype "passive"))
    )
    (net (code "75") (name "Net-(LED82-PadA)") (class "Default")
      (node (ref "LED82") (pin "A") (pinfunction "A_A") (pintype "passive"))
      (node (ref "LED83") (pin "C") (pinfunction "C_C") (pintype "passive"))
    )
    (net (code "76") (name "Net-(LED82-PadC)") (class "Default")
      (node (ref "LED82") (pin "C") (pinfunction "C_C") (pintype "passive"))
      (node (ref "LED83") (pin "A") (pinfunction "A_A") (pintype "passive"))
    )
    (net (code "77") (name "Net-(LED84-PadA)") (class "Default")
      (node (ref "LED84") (pin "A") (pinfunction "A_A") (pintype "passive"))
      (node (ref "LED85") (pin "C") (pinfunction "C_C") (pintype "passive"))
    )
    (net (code "78") (name "Net-(LED84-PadC)") (class "Default")
      (node (ref "LED84") (pin "C") (pinfunction "C_C") (pintype "passive"))
      (node (ref "LED85") (pin "A") (pinfunction "A_A") (pintype "passive"))
    )
    (net (code "79") (name "Net-(LED86-PadA)") (class "Default")
      (node (ref "LED86") (pin "A") (pinfunction "A_A") (pintype "passive"))
      (node (ref "LED87") (pin "C") (pinfunction "C_C") (pintype "passive"))
    )
    (net (code "80") (name "Net-(LED86-PadC)") (class "Default")
      (node (ref "LED86") (pin "C") (pinfunction "C_C") (pintype "passive"))
      (node (ref "LED87") (pin "A") (pinfunction "A_A") (pintype "passive"))
    )
    (net (code "81") (name "Net-(LED88-PadA)") (class "Default")
      (node (ref "LED88") (pin "A") (pinfunction "A_A") (pintype "passive"))
      (node (ref "LED89") (pin "C") (pinfunction "C_C") (pintype "passive"))
    )
    (net (code "82") (name "Net-(LED88-PadC)") (class "Default")
      (node (ref "LED88") (pin "C") (pinfunction "C_C") (pintype "passive"))
      (node (ref "LED89") (pin "A") (pinfunction "A_A") (pintype "passive"))
    )
    (net (code "83") (name "Net-(LED90-PadA)") (class "Default")
      (node (ref "LED90") (pin "A") (pinfunction "A_A") (pintype "passive"))
      (node (ref "LED91") (pin "C") (pinfunction "C_C") (pintype "passive"))
    )
    (net (code "84") (name "Net-(LED90-PadC)") (class "Default")
      (node (ref "LED90") (pin "C") (pinfunction "C_C") (pintype "passive"))
      (node (ref "LED91") (pin "A") (pinfunction "A_A") (pintype "passive"))
    )
    (net (code "85") (name "Net-(LED92-PadA)") (class "Default")
      (node (ref "LED92") (pin "A") (pinfunction "A_A") (pintype "passive"))
      (node (ref "LED93") (pin "C") (pinfunction "C_C") (pintype "passive"))
    )
    (net (code "86") (name "Net-(LED92-PadC)") (class "Default")
      (node (ref "LED92") (pin "C") (pinfunction "C_C") (pintype "passive"))
      (node (ref "LED93") (pin "A") (pinfunction "A_A") (pintype "passive"))
    )
    (net (code "87") (name "Net-(LED94-PadA)") (class "Default")
      (node (ref "LED94") (pin "A") (pinfunction "A_A") (pintype "passive"))
      (node (ref "LED95") (pin "C") (pinfunction "C_C") (pintype "passive"))
    )
    (net (code "88") (name "Net-(LED94-PadC)") (class "Default")
      (node (ref "LED94") (pin "C") (pinfunction "C_C") (pintype "passive"))
      (node (ref "LED95") (pin "A") (pinfunction "A_A") (pintype "passive"))
    )
    (net (code "89") (name "Net-(LED96-PadA)") (class "Default")
      (node (ref "LED96") (pin "A") (pinfunction "A_A") (pintype "passive"))
      (node (ref "LED97") (pin "C") (pinfunction "C_C") (pintype "passive"))
    )
    (net (code "90") (name "Net-(LED96-PadC)") (class "Default")
      (node (ref "LED96") (pin "C") (pinfunction "C_C") (pintype "passive"))
      (node (ref "LED97") (pin "A") (pinfunction "A_A") (pintype "passive"))
    )
    (net (code "91") (name "Net-(LED98-PadA)") (class "Default")
      (node (ref "LED98") (pin "A") (pinfunction "A_A") (pintype "passive"))
      (node (ref "LED99") (pin "C") (pinfunction "C_C") (pintype "passive"))
    )
    (net (code "92") (name "Net-(LED98-PadC)") (class "Default")
      (node (ref "LED98") (pin "C") (pinfunction "C_C") (pintype "passive"))
      (node (ref "LED99") (pin "A") (pinfunction "A_A") (pintype "passive"))
    )
    (net (code "93") (name "Net-(LED100-PadA)") (class "Default")
      (node (ref "LED100") (pin "A") (pinfunction "A_A") (pintype "passive"))
      (node (ref "LED101") (pin "C") (pinfunction "C_C") (pintype "passive"))
    )
    (net (code "94") (name "Net-(LED100-PadC)") (class "Default")
      (node (ref "LED100") (pin "C") (pinfunction "C_C") (pintype "passive"))
      (node (ref "LED101") (pin "A") (pinfunction "A_A") (pintype "passive"))
    )
    (net (code "95") (name "Net-(LED102-PadA)") (class "Default")
      (node (ref "LED102") (pin "A") (pinfunction "A_A") (pintype "passive"))
      (node (ref "LED103") (pin "C") (pinfunction "C_C") (pintype "passive"))
    )
    (net (code "96") (name "Net-(LED102-PadC)") (class "Default")
      (node (ref "LED102") (pin "C") (pinfunction "C_C") (pintype "passive"))
      (node (ref "LED103") (pin "A") (pinfunction "A_A") (pintype "passive"))
    )
    (net (code "97") (name "Net-(LED104-PadA)") (class "Default")
      (node (ref "LED104") (pin "A") (pinfunction "A_A") (pintype "passive"))
      (node (ref "LED105") (pin "C") (pinfunction "C_C") (pintype "passive"))
    )
    (net (code "98") (name "Net-(LED104-PadC)") (class "Default")
      (node (ref "LED104") (pin "C") (pinfunction "C_C") (pintype "passive"))
      (node (ref "LED105") (pin "A") (pinfunction "A_A") (pintype "passive"))
    )
    (net (code "99") (name "Net-(LED106-PadA)") (class "Default")
      (node (ref "LED106") (pin "A") (pinfunction "A_A") (pintype "passive"))
      (node (ref "LED107") (pin "C") (pinfunction "C_C") (pintype "passive"))
    )
    (net (code "100") (name "Net-(LED106-PadC)") (class "Default")
      (node (ref "LED106") (pin "C") (pinfunction "C_C") (pintype "passive"))
      (node (ref "LED107") (pin "A") (pinfunction "A_A") (pintype "passive"))
    )
    (net (code "101") (name "Net-(LED108-PadA)") (class "Default")
      (node (ref "LED108") (pin "A") (pinfunction "A_A") (pintype "passive"))
      (node (ref "LED109") (pin "C") (pinfunction "C_C") (pintype "passive"))
    )
    (net (code "102") (name "Net-(LED108-PadC)") (class "Default")
      (node (ref "LED108") (pin "C") (pinfunction "C_C") (pintype "passive"))
      (node (ref "LED109") (pin "A") (pinfunction "A_A") (pintype "passive"))
    )
    (net (code "103") (name "Net-(LED110-PadA)") (class "Default")
      (node (ref "LED110") (pin "A") (pinfunction "A_A") (pintype "passive"))
      (node (ref "LED111") (pin "C") (pinfunction "C_C") (pintype "passive"))
    )
    (net (code "104") (name "Net-(LED110-PadC)") (class "Default")
      (node (ref "LED110") (pin "C") (pinfunction "C_C") (pintype "passive"))
      (node (ref "LED111") (pin "A") (pinfunction "A_A") (pintype "passive"))
    )
    (net (code "105") (name "Net-(LED112-PadA)") (class "Default")
      (node (ref "LED112") (pin "A") (pinfunction "A_A") (pintype "passive"))
      (node (ref "LED113") (pin "C") (pinfunction "C_C") (pintype "passive"))
    )
    (net (code "106") (name "Net-(LED112-PadC)") (class "Default")
      (node (ref "LED112") (pin "C") (pinfunction "C_C") (pintype "passive"))
      (node (ref "LED113") (pin "A") (pinfunction "A_A") (pintype "passive"))
    )
    (net (code "107") (name "Net-(LED114-PadA)") (class "Default")
      (node (ref "LED114") (pin "A") (pinfunction "A_A") (pintype "passive"))
      (node (ref "LED115") (pin "C") (pinfunction "C_C") (pintype "passive"))
    )
    (net (code "108") (name "Net-(LED114-PadC)") (class "Default")
      (node (ref "LED114") (pin "C") (pinfunction "C_C") (pintype "passive"))
      (node (ref "LED115") (pin "A") (pinfunction "A_A") (pintype "passive"))
    )
    (net (code "109") (name "Net-(LED116-PadA)") (class "Default")
      (node (ref "LED116") (pin "A") (pinfunction "A_A") (pintype "passive"))
      (node (ref "LED117") (pin "C") (pinfunction "C_C") (pintype "passive"))
    )
    (net (code "110") (name "Net-(LED116-PadC)") (class "Default")
      (node (ref "LED116") (pin "C") (pinfunction "C_C") (pintype "passive"))
      (node (ref "LED117") (pin "A") (pinfunction "A_A") (pintype "passive"))
    )
    (net (code "111") (name "Net-(LED118-PadA)") (class "Default")
      (node (ref "LED118") (pin "A") (pinfunction "A_A") (pintype "passive"))
      (node (ref "LED119") (pin "C") (pinfunction "C_C") (pintype "passive"))
    )
    (net (code "112") (name "Net-(LED118-PadC)") (class "Default")
      (node (ref "LED118") (pin "C") (pinfunction "C_C") (pintype "passive"))
      (node (ref "LED119") (pin "A") (pinfunction "A_A") (pintype "passive"))
    )
    (net (code "113") (name "Net-(LED120-PadA)") (class "Default")
      (node (ref "LED120") (pin "A") (pinfunction "A_A") (pintype "passive"))
      (node (ref "LED61") (pin "C") (pinfunction "C_C") (pintype "passive"))
    )
    (net (code "114") (name "Net-(LED120-PadC)") (class "Default")
      (node (ref "LED120") (pin "C") (pinfunction "C_C") (pintype "passive"))
      (node (ref "LED61") (pin "A") (pinfunction "A_A") (pintype "passive"))
    )
    (net (code "115") (name "Net-(LED121-PadC)") (class "Default")
      (node (ref "LED121") (pin "C") (pinfunction "C_C") (pintype "passive"))
      (node (ref "LED122") (pin "A") (pinfunction "A_A") (pintype "passive"))
      (node (ref "LED123") (pin "C") (pinfunction "C_C") (pintype "passive"))
      (node (ref "LED124") (pin "A") (pinfunction "A_A") (pintype "passive"))
      (node (ref "LED125") (pin "C") (pinfunction "C_C") (pintype "passive"))
      (node (ref "LED126") (pin "A") (pinfunction "A_A") (pintype "passive"))
      (node (ref "LED127") (pin "C") (pinfunction "C_C") (pintype "passive"))
      (node (ref "LED128") (pin "A") (pinfunction "A_A") (pintype "passive"))
      (node (ref "LED129") (pin "C") (pinfunction "C_C") (pintype "passive"))
      (node (ref "LED130") (pin "A") (pinfunction "A_A") (pintype "passive"))
      (node (ref "SV1") (pin "1") (pinfunction "1_1") (pintype "passive"))
    )
    (net (code "116") (name "Net-(LED123-PadA)") (class "Default")
      (node (ref "LED123") (pin "A") (pinfunction "A_A") (pintype "passive"))
      (node (ref "LED124") (pin "C") (pinfunction "C_C") (pintype "passive"))
      (node (ref "LED3") (pin "A") (pinfunction "A_A") (pintype "passive"))
      (node (ref "LED4") (pin "C") (pinfunction "C_C") (pintype "passive"))
      (node (ref "LED64") (pin "C") (pinfunction "C_C") (pintype "passive"))
      (node (ref "LED65") (pin "A") (pinfunction "A_A") (pintype "passive"))
    )
    (net (code "117") (name "Net-(LED125-PadA)") (class "Default")
      (node (ref "LED125") (pin "A") (pinfunction "A_A") (pintype "passive"))
      (node (ref "LED126") (pin "C") (pinfunction "C_C") (pintype "passive"))
      (node (ref "LED5") (pin "A") (pinfunction "A_A") (pintype "passive"))
      (node (ref "LED6") (pin "C") (pinfunction "C_C") (pintype "passive"))
      (node (ref "LED66") (pin "C") (pinfunction "C_C") (pintype "passive"))
      (node (ref "LED67") (pin "A") (pinfunction "A_A") (pintype "passive"))
    )
    (net (code "118") (name "Net-(LED127-PadA)") (class "Default")
      (node (ref "LED127") (pin "A") (pinfunction "A_A") (pintype "passive"))
      (node (ref "LED128") (pin "C") (pinfunction "C_C") (pintype "passive"))
      (node (ref "LED68") (pin "C") (pinfunction "C_C") (pintype "passive"))
      (node (ref "LED69") (pin "A") (pinfunction "A_A") (pintype "passive"))
      (node (ref "LED7") (pin "A") (pinfunction "A_A") (pintype "passive"))
      (node (ref "LED8") (pin "C") (pinfunction "C_C") (pintype "passive"))
    )
    (net (code "119") (name "Net-(LED131-PadA)") (class "Default")
      (node (ref "LED131") (pin "A") (pinfunction "A_A") (pintype "passive"))
      (node (ref "LED132") (pin "C") (pinfunction "C_C") (pintype "passive"))
    )
    (net (code "120") (name "Net-(LED131-PadC)") (class "Default")
      (node (ref "LED131") (pin "C") (pinfunction "C_C") (pintype "passive"))
      (node (ref "LED132") (pin "A") (pinfunction "A_A") (pintype "passive"))
    )
    (net (code "121") (name "Net-(LED133-PadA)") (class "Default")
      (node (ref "LED133") (pin "A") (pinfunction "A_A") (pintype "passive"))
      (node (ref "LED134") (pin "C") (pinfunction "C_C") (pintype "passive"))
    )
    (net (code "122") (name "Net-(LED133-PadC)") (class "Default")
      (node (ref "LED133") (pin "C") (pinfunction "C_C") (pintype "passive"))
      (node (ref "LED134") (pin "A") (pinfunction "A_A") (pintype "passive"))
    )
    (net (code "123") (name "Net-(LED135-PadA)") (class "Default")
      (node (ref "LED135") (pin "A") (pinfunction "A_A") (pintype "passive"))
      (node (ref "LED136") (pin "C") (pinfunction "C_C") (pintype "passive"))
    )
    (net (code "124") (name "Net-(LED135-PadC)") (class "Default")
      (node (ref "LED135") (pin "C") (pinfunction "C_C") (pintype "passive"))
      (node (ref "LED136") (pin "A") (pinfunction "A_A") (pintype "passive"))
    )
    (net (code "125") (name "Net-(LED137-PadA)") (class "Default")
      (node (ref "LED137") (pin "A") (pinfunction "A_A") (pintype "passive"))
      (node (ref "LED138") (pin "C") (pinfunction "C_C") (pintype "passive"))
    )
    (net (code "126") (name "Net-(LED137-PadC)") (class "Default")
      (node (ref "LED137") (pin "C") (pinfunction "C_C") (pintype "passive"))
      (node (ref "LED138") (pin "A") (pinfunction "A_A") (pintype "passive"))
    )
    (net (code "127") (name "Net-(LED139-PadA)") (class "Default")
      (node (ref "LED139") (pin "A") (pinfunction "A_A") (pintype "passive"))
      (node (ref "LED140") (pin "C") (pinfunction "C_C") (pintype "passive"))
    )
    (net (code "128") (name "Net-(LED139-PadC)") (class "Default")
      (node (ref "LED139") (pin "C") (pinfunction "C_C") (pintype "passive"))
      (node (ref "LED140") (pin "A") (pinfunction "A_A") (pintype "passive"))
    )
    (net (code "129") (name "Net-(LED141-PadA)") (class "Default")
      (node (ref "LED141") (pin "A") (pinfunction "A_A") (pintype "passive"))
      (node (ref "LED142") (pin "C") (pinfunction "C_C") (pintype "passive"))
    )
    (net (code "130") (name "Net-(LED141-PadC)") (class "Default")
      (node (ref "LED141") (pin "C") (pinfunction "C_C") (pintype "passive"))
      (node (ref "LED142") (pin "A") (pinfunction "A_A") (pintype "passive"))
    )
    (net (code "131") (name "Net-(LED143-PadA)") (class "Default")
      (node (ref "LED143") (pin "A") (pinfunction "A_A") (pintype "passive"))
      (node (ref "LED144") (pin "C") (pinfunction "C_C") (pintype "passive"))
    )
    (net (code "132") (name "Net-(LED143-PadC)") (class "Default")
      (node (ref "LED143") (pin "C") (pinfunction "C_C") (pintype "passive"))
      (node (ref "LED144") (pin "A") (pinfunction "A_A") (pintype "passive"))
    )
    (net (code "133") (name "Net-(LED145-PadA)") (class "Default")
      (node (ref "LED145") (pin "A") (pinfunction "A_A") (pintype "passive"))
      (node (ref "LED146") (pin "C") (pinfunction "C_C") (pintype "passive"))
    )
    (net (code "134") (name "Net-(LED145-PadC)") (class "Default")
      (node (ref "LED145") (pin "C") (pinfunction "C_C") (pintype "passive"))
      (node (ref "LED146") (pin "A") (pinfunction "A_A") (pintype "passive"))
    )
    (net (code "135") (name "Net-(LED147-PadA)") (class "Default")
      (node (ref "LED147") (pin "A") (pinfunction "A_A") (pintype "passive"))
      (node (ref "LED148") (pin "C") (pinfunction "C_C") (pintype "passive"))
    )
    (net (code "136") (name "Net-(LED147-PadC)") (class "Default")
      (node (ref "LED147") (pin "C") (pinfunction "C_C") (pintype "passive"))
      (node (ref "LED148") (pin "A") (pinfunction "A_A") (pintype "passive"))
    )
    (net (code "137") (name "Net-(LED149-PadA)") (class "Default")
      (node (ref "LED149") (pin "A") (pinfunction "A_A") (pintype "passive"))
      (node (ref "LED150") (pin "C") (pinfunction "C_C") (pintype "passive"))
    )
    (net (code "138") (name "Net-(LED149-PadC)") (class "Default")
      (node (ref "LED149") (pin "C") (pinfunction "C_C") (pintype "passive"))
      (node (ref "LED150") (pin "A") (pinfunction "A_A") (pintype "passive"))
    )
    (net (code "139") (name "Net-(LED151-PadA)") (class "Default")
      (node (ref "LED151") (pin "A") (pinfunction "A_A") (pintype "passive"))
      (node (ref "LED152") (pin "C") (pinfunction "C_C") (pintype "passive"))
    )
    (net (code "140") (name "Net-(LED151-PadC)") (class "Default")
      (node (ref "LED151") (pin "C") (pinfunction "C_C") (pintype "passive"))
      (node (ref "LED152") (pin "A") (pinfunction "A_A") (pintype "passive"))
    )
    (net (code "141") (name "Net-(LED153-PadA)") (class "Default")
      (node (ref "LED153") (pin "A") (pinfunction "A_A") (pintype "passive"))
      (node (ref "LED154") (pin "C") (pinfunction "C_C") (pintype "passive"))
    )
    (net (code "142") (name "Net-(LED153-PadC)") (class "Default")
      (node (ref "LED153") (pin "C") (pinfunction "C_C") (pintype "passive"))
      (node (ref "LED154") (pin "A") (pinfunction "A_A") (pintype "passive"))
    )
    (net (code "143") (name "Net-(LED155-PadA)") (class "Default")
      (node (ref "LED155") (pin "A") (pinfunction "A_A") (pintype "passive"))
      (node (ref "LED156") (pin "C") (pinfunction "C_C") (pintype "passive"))
    )
    (net (code "144") (name "Net-(LED155-PadC)") (class "Default")
      (node (ref "LED155") (pin "C") (pinfunction "C_C") (pintype "passive"))
      (node (ref "LED156") (pin "A") (pinfunction "A_A") (pintype "passive"))
    )
    (net (code "145") (name "Net-(LED157-PadA)") (class "Default")
      (node (ref "LED157") (pin "A") (pinfunction "A_A") (pintype "passive"))
      (node (ref "LED158") (pin "C") (pinfunction "C_C") (pintype "passive"))
    )
    (net (code "146") (name "Net-(LED157-PadC)") (class "Default")
      (node (ref "LED157") (pin "C") (pinfunction "C_C") (pintype "passive"))
      (node (ref "LED158") (pin "A") (pinfunction "A_A") (pintype "passive"))
    )
    (net (code "147") (name "Net-(LED159-PadA)") (class "Default")
      (node (ref "LED159") (pin "A") (pinfunction "A_A") (pintype "passive"))
      (node (ref "LED160") (pin "C") (pinfunction "C_C") (pintype "passive"))
    )
    (net (code "148") (name "Net-(LED159-PadC)") (class "Default")
      (node (ref "LED159") (pin "C") (pinfunction "C_C") (pintype "passive"))
      (node (ref "LED160") (pin "A") (pinfunction "A_A") (pintype "passive"))
    )
    (net (code "149") (name "Net-(LED161-PadA)") (class "Default")
      (node (ref "LED161") (pin "A") (pinfunction "A_A") (pintype "passive"))
      (node (ref "LED162") (pin "C") (pinfunction "C_C") (pintype "passive"))
    )
    (net (code "150") (name "Net-(LED161-PadC)") (class "Default")
      (node (ref "LED161") (pin "C") (pinfunction "C_C") (pintype "passive"))
      (node (ref "LED162") (pin "A") (pinfunction "A_A") (pintype "passive"))
    )
    (net (code "151") (name "Net-(LED163-PadA)") (class "Default")
      (node (ref "LED163") (pin "A") (pinfunction "A_A") (pintype "passive"))
      (node (ref "LED164") (pin "C") (pinfunction "C_C") (pintype "passive"))
    )
    (net (code "152") (name "Net-(LED163-PadC)") (class "Default")
      (node (ref "LED163") (pin "C") (pinfunction "C_C") (pintype "passive"))
      (node (ref "LED164") (pin "A") (pinfunction "A_A") (pintype "passive"))
    )
    (net (code "153") (name "Net-(LED165-PadA)") (class "Default")
      (node (ref "LED165") (pin "A") (pinfunction "A_A") (pintype "passive"))
      (node (ref "LED166") (pin "C") (pinfunction "C_C") (pintype "passive"))
    )
    (net (code "154") (name "Net-(LED165-PadC)") (class "Default")
      (node (ref "LED165") (pin "C") (pinfunction "C_C") (pintype "passive"))
      (node (ref "LED166") (pin "A") (pinfunction "A_A") (pintype "passive"))
    )
    (net (code "155") (name "Net-(LED167-PadA)") (class "Default")
      (node (ref "LED167") (pin "A") (pinfunction "A_A") (pintype "passive"))
      (node (ref "LED168") (pin "C") (pinfunction "C_C") (pintype "passive"))
    )
    (net (code "156") (name "Net-(LED167-PadC)") (class "Default")
      (node (ref "LED167") (pin "C") (pinfunction "C_C") (pintype "passive"))
      (node (ref "LED168") (pin "A") (pinfunction "A_A") (pintype "passive"))
    )
    (net (code "157") (name "Net-(LED169-PadA)") (class "Default")
      (node (ref "LED169") (pin "A") (pinfunction "A_A") (pintype "passive"))
      (node (ref "LED170") (pin "C") (pinfunction "C_C") (pintype "passive"))
    )
    (net (code "158") (name "Net-(LED169-PadC)") (class "Default")
      (node (ref "LED169") (pin "C") (pinfunction "C_C") (pintype "passive"))
      (node (ref "LED170") (pin "A") (pinfunction "A_A") (pintype "passive"))
    )
    (net (code "159") (name "Net-(LED171-PadA)") (class "Default")
      (node (ref "LED171") (pin "A") (pinfunction "A_A") (pintype "passive"))
      (node (ref "LED172") (pin "C") (pinfunction "C_C") (pintype "passive"))
    )
    (net (code "160") (name "Net-(LED171-PadC)") (class "Default")
      (node (ref "LED171") (pin "C") (pinfunction "C_C") (pintype "passive"))
      (node (ref "LED172") (pin "A") (pinfunction "A_A") (pintype "passive"))
    )
    (net (code "161") (name "Net-(LED173-PadA)") (class "Default")
      (node (ref "LED173") (pin "A") (pinfunction "A_A") (pintype "passive"))
      (node (ref "LED174") (pin "C") (pinfunction "C_C") (pintype "passive"))
    )
    (net (code "162") (name "Net-(LED173-PadC)") (class "Default")
      (node (ref "LED173") (pin "C") (pinfunction "C_C") (pintype "passive"))
      (node (ref "LED174") (pin "A") (pinfunction "A_A") (pintype "passive"))
    )
    (net (code "163") (name "Net-(LED175-PadA)") (class "Default")
      (node (ref "LED175") (pin "A") (pinfunction "A_A") (pintype "passive"))
      (node (ref "LED176") (pin "C") (pinfunction "C_C") (pintype "passive"))
    )
    (net (code "164") (name "Net-(LED175-PadC)") (class "Default")
      (node (ref "LED175") (pin "C") (pinfunction "C_C") (pintype "passive"))
      (node (ref "LED176") (pin "A") (pinfunction "A_A") (pintype "passive"))
    )
    (net (code "165") (name "Net-(LED177-PadA)") (class "Default")
      (node (ref "LED177") (pin "A") (pinfunction "A_A") (pintype "passive"))
      (node (ref "LED178") (pin "C") (pinfunction "C_C") (pintype "passive"))
    )
    (net (code "166") (name "Net-(LED177-PadC)") (class "Default")
      (node (ref "LED177") (pin "C") (pinfunction "C_C") (pintype "passive"))
      (node (ref "LED178") (pin "A") (pinfunction "A_A") (pintype "passive"))
    )
    (net (code "167") (name "Net-(LED179-PadA)") (class "Default")
      (node (ref "LED179") (pin "A") (pinfunction "A_A") (pintype "passive"))
      (node (ref "LED180") (pin "C") (pinfunction "C_C") (pintype "passive"))
    )
    (net (code "168") (name "Net-(LED179-PadC)") (class "Default")
      (node (ref "LED179") (pin "C") (pinfunction "C_C") (pintype "passive"))
      (node (ref "LED180") (pin "A") (pinfunction "A_A") (pintype "passive"))
    )
    (net (code "169") (name "unconnected-(IC1A-A-Pad10)") (class "Default")
      (node (ref "IC1") (pin "10") (pinfunction "A_10") (pintype "input"))
    )
    (net (code "170") (name "unconnected-(IC1A-B-Pad11)") (class "Default")
      (node (ref "IC1") (pin "11") (pinfunction "B_11") (pintype "input"))
    )
    (net (code "171") (name "unconnected-(IC1A-C-Pad14)") (class "Default")
      (node (ref "IC1") (pin "14") (pinfunction "C_14") (pintype "input"))
    )
    (net (code "172") (name "unconnected-(IC1A-D-Pad13)") (class "Default")
      (node (ref "IC1") (pin "13") (pinfunction "D_13") (pintype "input"))
    )
    (net (code "173") (name "unconnected-(IC1A-INH-Pad15)") (class "Default")
      (node (ref "IC1") (pin "15") (pinfunction "INH_15") (pintype "input"))
    )
    (net (code "174") (name "unconnected-(IC1A-X-Pad1)") (class "Default")
      (node (ref "IC1") (pin "1") (pinfunction "X_1") (pintype "output"))
    )
    (net (code "175") (name "unconnected-(IC1A-X0-Pad9)") (class "Default")
      (node (ref "IC1") (pin "9") (pinfunction "X0_9") (pintype "input"))
    )
    (net (code "176") (name "unconnected-(IC1A-X1-Pad8)") (class "Default")
      (node (ref "IC1") (pin "8") (pinfunction "X1_8") (pintype "input"))
    )
    (net (code "177") (name "unconnected-(IC1A-X2-Pad7)") (class "Default")
      (node (ref "IC1") (pin "7") (pinfunction "X2_7") (pintype "input"))
    )
    (net (code "178") (name "unconnected-(IC1A-X3-Pad6)") (class "Default")
      (node (ref "IC1") (pin "6") (pinfunction "X3_6") (pintype "input"))
    )
    (net (code "179") (name "unconnected-(IC1A-X4-Pad5)") (class "Default")
      (node (ref "IC1") (pin "5") (pinfunction "X4_5") (pintype "input"))
    )
    (net (code "180") (name "unconnected-(IC1A-X5-Pad4)") (class "Default")
      (node (ref "IC1") (pin "4") (pinfunction "X5_4") (pintype "input"))
    )
    (net (code "181") (name "unconnected-(IC1A-X6-Pad3)") (class "Default")
      (node (ref "IC1") (pin "3") (pinfunction "X6_3") (pintype "input"))
    )
    (net (code "182") (name "unconnected-(IC1A-X7-Pad2)") (class "Default")
      (node (ref "IC1") (pin "2") (pinfunction "X7_2") (pintype "input"))
    )
    (net (code "183") (name "unconnected-(IC1A-X8-Pad23)") (class "Default")
      (node (ref "IC1") (pin "23") (pinfunction "X8_23") (pintype "input"))
    )
    (net (code "184") (name "unconnected-(IC1A-X9-Pad22)") (class "Default")
      (node (ref "IC1") (pin "22") (pinfunction "X9_22") (pintype "input"))
    )
    (net (code "185") (name "unconnected-(IC1A-X10-Pad21)") (class "Default")
      (node (ref "IC1") (pin "21") (pinfunction "X10_21") (pintype "input"))
    )
    (net (code "186") (name "unconnected-(IC1A-X11-Pad20)") (class "Default")
      (node (ref "IC1") (pin "20") (pinfunction "X11_20") (pintype "input"))
    )
    (net (code "187") (name "unconnected-(IC1A-X12-Pad19)") (class "Default")
      (node (ref "IC1") (pin "19") (pinfunction "X12_19") (pintype "input"))
    )
    (net (code "188") (name "unconnected-(IC1A-X13-Pad18)") (class "Default")
      (node (ref "IC1") (pin "18") (pinfunction "X13_18") (pintype "input"))
    )
    (net (code "189") (name "unconnected-(IC1A-X14-Pad17)") (class "Default")
      (node (ref "IC1") (pin "17") (pinfunction "X14_17") (pintype "input"))
    )
    (net (code "190") (name "unconnected-(IC1A-X15-Pad16)") (class "Default")
      (node (ref "IC1") (pin "16") (pinfunction "X15_16") (pintype "input"))
    )
    (net (code "191") (name "unconnected-(IC2A-A-Pad10)") (class "Default")
      (node (ref "IC2") (pin "10") (pinfunction "A_10") (pintype "input"))
    )
    (net (code "192") (name "unconnected-(IC2A-B-Pad11)") (class "Default")
      (node (ref "IC2") (pin "11") (pinfunction "B_11") (pintype "input"))
    )
    (net (code "193") (name "unconnected-(IC2A-C-Pad14)") (class "Default")
      (node (ref "IC2") (pin "14") (pinfunction "C_14") (pintype "input"))
    )
    (net (code "194") (name "unconnected-(IC2A-D-Pad13)") (class "Default")
      (node (ref "IC2") (pin "13") (pinfunction "D_13") (pintype "input"))
    )
    (net (code "195") (name "unconnected-(IC2A-INH-Pad15)") (class "Default")
      (node (ref "IC2") (pin "15") (pinfunction "INH_15") (pintype "input"))
    )
    (net (code "196") (name "unconnected-(IC2A-X-Pad1)") (class "Default")
      (node (ref "IC2") (pin "1") (pinfunction "X_1") (pintype "output"))
    )
    (net (code "197") (name "unconnected-(IC2A-X0-Pad9)") (class "Default")
      (node (ref "IC2") (pin "9") (pinfunction "X0_9") (pintype "input"))
    )
    (net (code "198") (name "unconnected-(IC2A-X1-Pad8)") (class "Default")
      (node (ref "IC2") (pin "8") (pinfunction "X1_8") (pintype "input"))
    )
    (net (code "199") (name "unconnected-(IC2A-X2-Pad7)") (class "Default")
      (node (ref "IC2") (pin "7") (pinfunction "X2_7") (pintype "input"))
    )
    (net (code "200") (name "unconnected-(IC2A-X3-Pad6)") (class "Default")
      (node (ref "IC2") (pin "6") (pinfunction "X3_6") (pintype "input"))
    )
    (net (code "201") (name "unconnected-(IC2A-X4-Pad5)") (class "Default")
      (node (ref "IC2") (pin "5") (pinfunction "X4_5") (pintype "input"))
    )
    (net (code "202") (name "unconnected-(IC2A-X5-Pad4)") (class "Default")
      (node (ref "IC2") (pin "4") (pinfunction "X5_4") (pintype "input"))
    )
    (net (code "203") (name "unconnected-(IC2A-X6-Pad3)") (class "Default")
      (node (ref "IC2") (pin "3") (pinfunction "X6_3") (pintype "input"))
    )
    (net (code "204") (name "unconnected-(IC2A-X7-Pad2)") (class "Default")
      (node (ref "IC2") (pin "2") (pinfunction "X7_2") (pintype "input"))
    )
    (net (code "205") (name "unconnected-(IC2A-X8-Pad23)") (class "Default")
      (node (ref "IC2") (pin "23") (pinfunction "X8_23") (pintype "input"))
    )
    (net (code "206") (name "unconnected-(IC2A-X9-Pad22)") (class "Default")
      (node (ref "IC2") (pin "22") (pinfunction "X9_22") (pintype "input"))
    )
    (net (code "207") (name "unconnected-(IC2A-X10-Pad21)") (class "Default")
      (node (ref "IC2") (pin "21") (pinfunction "X10_21") (pintype "input"))
    )
    (net (code "208") (name "unconnected-(IC2A-X11-Pad20)") (class "Default")
      (node (ref "IC2") (pin "20") (pinfunction "X11_20") (pintype "input"))
    )
    (net (code "209") (name "unconnected-(IC2A-X12-Pad19)") (class "Default")
      (node (ref "IC2") (pin "19") (pinfunction "X12_19") (pintype "input"))
    )
    (net (code "210") (name "unconnected-(IC2A-X13-Pad18)") (class "Default")
      (node (ref "IC2") (pin "18") (pinfunction "X13_18") (pintype "input"))
    )
    (net (code "211") (name "unconnected-(IC2A-X14-Pad17)") (class "Default")
      (node (ref "IC2") (pin "17") (pinfunction "X14_17") (pintype "input"))
    )
    (net (code "212") (name "unconnected-(IC2A-X15-Pad16)") (class "Default")
      (node (ref "IC2") (pin "16") (pinfunction "X15_16") (pintype "input"))
    )
    (net (code "213") (name "unconnected-(SV2-Pad1)") (class "Default")
      (node (ref "SV2") (pin "1") (pinfunction "1_1") (pintype "passive"))
    )
    (net (code "214") (name "unconnected-(SV2-Pad2)") (class "Default")
      (node (ref "SV2") (pin "2") (pinfunction "2_2") (pintype "passive"))
    )
    (net (code "215") (name "unconnected-(SV2-Pad3)") (class "Default")
      (node (ref "SV2") (pin "3") (pinfunction "3_3") (pintype "passive"))
    )
    (net (code "216") (name "unconnected-(SV3-Pad1)") (class "Default")
      (node (ref "SV3") (pin "1") (pinfunction "1_1") (pintype "passive"))
    )
    (net (code "217") (name "unconnected-(SV3-Pad2)") (class "Default")
      (node (ref "SV3") (pin "2") (pinfunction "2_2") (pintype "passive"))
    )
    (net (code "218") (name "unconnected-(SV3-Pad3)") (class "Default")
      (node (ref "SV3") (pin "3") (pinfunction "3_3") (pintype "passive"))
    )
    (net (code "219") (name "unconnected-(SV4-Pad1)") (class "Default")
      (node (ref "SV4") (pin "1") (pinfunction "1_1") (pintype "passive"))
    )
    (net (code "220") (name "unconnected-(SV4-Pad2)") (class "Default")
      (node (ref "SV4") (pin "2") (pinfunction "2_2") (pintype "passive"))
    )
    (net (code "221") (name "unconnected-(SV4-Pad3)") (class "Default")
      (node (ref "SV4") (pin "3") (pinfunction "3_3") (pintype "passive"))
    )
    (net (code "222") (name "unconnected-(U1-(A8)PC0-Pad53)") (class "Default")
      (node (ref "U1") (pin "53") (pinfunction "(A8)PC0_53") (pintype "bidirectional"))
    )
    (net (code "223") (name "unconnected-(U1-(A9)PC1-Pad54)") (class "Default")
      (node (ref "U1") (pin "54") (pinfunction "(A9)PC1_54") (pintype "bidirectional"))
    )
    (net (code "224") (name "unconnected-(U1-(A10)PC2-Pad55)") (class "Default")
      (node (ref "U1") (pin "55") (pinfunction "(A10)PC2_55") (pintype "bidirectional"))
    )
    (net (code "225") (name "unconnected-(U1-(A11)PC3-Pad56)") (class "Default")
      (node (ref "U1") (pin "56") (pinfunction "(A11)PC3_56") (pintype "bidirectional"))
    )
    (net (code "226") (name "unconnected-(U1-(A12)PC4-Pad57)") (class "Default")
      (node (ref "U1") (pin "57") (pinfunction "(A12)PC4_57") (pintype "bidirectional"))
    )
    (net (code "227") (name "unconnected-(U1-(A13)PC5-Pad58)") (class "Default")
      (node (ref "U1") (pin "58") (pinfunction "(A13)PC5_58") (pintype "bidirectional"))
    )
    (net (code "228") (name "unconnected-(U1-(A14)PC6-Pad59)") (class "Default")
      (node (ref "U1") (pin "59") (pinfunction "(A14)PC6_59") (pintype "bidirectional"))
    )
    (net (code "229") (name "unconnected-(U1-(A15)PC7-Pad60)") (class "Default")
      (node (ref "U1") (pin "60") (pinfunction "(A15)PC7_60") (pintype "bidirectional"))
    )
    (net (code "230") (name "unconnected-(U1-(AD0)PA0-Pad78)") (class "Default")
      (node (ref "U1") (pin "78") (pinfunction "(AD0)PA0_78") (pintype "bidirectional"))
    )
    (net (code "231") (name "unconnected-(U1-(AD1)PA1-Pad77)") (class "Default")
      (node (ref "U1") (pin "77") (pinfunction "(AD1)PA1_77") (pintype "bidirectional"))
    )
    (net (code "232") (name "unconnected-(U1-(AD2)PA2-Pad76)") (class "Default")
      (node (ref "U1") (pin "76") (pinfunction "(AD2)PA2_76") (pintype "bidirectional"))
    )
    (net (code "233") (name "unconnected-(U1-(AD3)PA3-Pad75)") (class "Default")
      (node (ref "U1") (pin "75") (pinfunction "(AD3)PA3_75") (pintype "bidirectional"))
    )
    (net (code "234") (name "unconnected-(U1-(AD4)PA4-Pad74)") (class "Default")
      (node (ref "U1") (pin "74") (pinfunction "(AD4)PA4_74") (pintype "bidirectional"))
    )
    (net (code "235") (name "unconnected-(U1-(AD5)PA5-Pad73)") (class "Default")
      (node (ref "U1") (pin "73") (pinfunction "(AD5)PA5_73") (pintype "bidirectional"))
    )
    (net (code "236") (name "unconnected-(U1-(AD6)PA6-Pad72)") (class "Default")
      (node (ref "U1") (pin "72") (pinfunction "(AD6)PA6_72") (pintype "bidirectional"))
    )
    (net (code "237") (name "unconnected-(U1-(AD7)PA7-Pad71)") (class "Default")
      (node (ref "U1") (pin "71") (pinfunction "(AD7)PA7_71") (pintype "bidirectional"))
    )
    (net (code "238") (name "unconnected-(U1-(ADC0)PF0-Pad97)") (class "Default")
      (node (ref "U1") (pin "97") (pinfunction "(ADC0)PF0_97") (pintype "bidirectional"))
    )
    (net (code "239") (name "unconnected-(U1-(ADC1)PF1-Pad96)") (class "Default")
      (node (ref "U1") (pin "96") (pinfunction "(ADC1)PF1_96") (pintype "bidirectional"))
    )
    (net (code "240") (name "unconnected-(U1-(ADC2)PF2-Pad95)") (class "Default")
      (node (ref "U1") (pin "95") (pinfunction "(ADC2)PF2_95") (pintype "bidirectional"))
    )
    (net (code "241") (name "unconnected-(U1-(ADC3)PF3-Pad94)") (class "Default")
      (node (ref "U1") (pin "94") (pinfunction "(ADC3)PF3_94") (pintype "bidirectional"))
    )
    (net (code "242") (name "unconnected-(U1-(ADC4{slash}TCK)PF4-Pad93)") (class "Default")
      (node (ref "U1") (pin "93") (pinfunction "(ADC4/TCK)PF4_93") (pintype "bidirectional"))
    )
    (net (code "243") (name "unconnected-(U1-(ADC5{slash}TMS)PF5-Pad92)") (class "Default")
      (node (ref "U1") (pin "92") (pinfunction "(ADC5/TMS)PF5_92") (pintype "bidirectional"))
    )
    (net (code "244") (name "unconnected-(U1-(ADC6{slash}TDO)PF6-Pad91)") (class "Default")
      (node (ref "U1") (pin "91") (pinfunction "(ADC6/TDO)PF6_91") (pintype "bidirectional"))
    )
    (net (code "245") (name "unconnected-(U1-(ADC7{slash}TDI)PF7-Pad90)") (class "Default")
      (node (ref "U1") (pin "90") (pinfunction "(ADC7/TDI)PF7_90") (pintype "bidirectional"))
    )
    (net (code "246") (name "unconnected-(U1-(ALE)PG2-Pad70)") (class "Default")
      (node (ref "U1") (pin "70") (pinfunction "(ALE)PG2_70") (pintype "bidirectional"))
    )
    (net (code "247") (name "unconnected-(U1-(CLKO{slash}ICP3{slash}INT7)PE7-Pad9)") (class "Default")
      (node (ref "U1") (pin "9") (pinfunction "(CLKO/ICP3/INT7)PE7_9") (pintype "bidirectional"))
    )
    (net (code "248") (name "unconnected-(U1-(ICP1)PD4-Pad47)") (class "Default")
      (node (ref "U1") (pin "47") (pinfunction "(ICP1)PD4_47") (pintype "bidirectional"))
    )
    (net (code "249") (name "unconnected-(U1-(MISO{slash}PCINT3)PB3-Pad22)") (class "Default")
      (node (ref "U1") (pin "22") (pinfunction "(MISO/PCINT3)PB3_22") (pintype "bidirectional"))
    )
    (net (code "250") (name "unconnected-(U1-(MOSI{slash}PCINT2)PB2-Pad21)") (class "Default")
      (node (ref "U1") (pin "21") (pinfunction "(MOSI/PCINT2)PB2_21") (pintype "bidirectional"))
    )
    (net (code "251") (name "unconnected-(U1-(OC0A{slash}OC1C{slash}PCINT7)PB7-Pad26)") (class "Default")
      (node (ref "U1") (pin "26") (pinfunction "(OC0A/OC1C/PCINT7)PB7_26") (pintype "bidirectional"))
    )
    (net (code "252") (name "unconnected-(U1-(OC0B)PG5-Pad1)") (class "Default")
      (node (ref "U1") (pin "1") (pinfunction "(OC0B)PG5_1") (pintype "bidirectional"))
    )
    (net (code "253") (name "unconnected-(U1-(OC1A{slash}PCINT5)PB5-Pad24)") (class "Default")
      (node (ref "U1") (pin "24") (pinfunction "(OC1A/PCINT5)PB5_24") (pintype "bidirectional"))
    )
    (net (code "254") (name "unconnected-(U1-(OC1B{slash}PCINT6)PB6-Pad25)") (class "Default")
      (node (ref "U1") (pin "25") (pinfunction "(OC1B/PCINT6)PB6_25") (pintype "bidirectional"))
    )
    (net (code "255") (name "unconnected-(U1-(OC2A{slash}PCINT4)PB4-Pad23)") (class "Default")
      (node (ref "U1") (pin "23") (pinfunction "(OC2A/PCINT4)PB4_23") (pintype "bidirectional"))
    )
    (net (code "256") (name "unconnected-(U1-(OC3A{slash}AIN1)PE3-Pad5)") (class "Default")
      (node (ref "U1") (pin "5") (pinfunction "(OC3A/AIN1)PE3_5") (pintype "bidirectional"))
    )
    (net (code "257") (name "unconnected-(U1-(OC3B{slash}INT4)PE4-Pad6)") (class "Default")
      (node (ref "U1") (pin "6") (pinfunction "(OC3B/INT4)PE4_6") (pintype "bidirectional"))
    )
    (net (code "258") (name "unconnected-(U1-(OC3C{slash}INT5)PE5-Pad7)") (class "Default")
      (node (ref "U1") (pin "7") (pinfunction "(OC3C/INT5)PE5_7") (pintype "bidirectional"))
    )
    (net (code "259") (name "unconnected-(U1-(RD)PG1-Pad52)") (class "Default")
      (node (ref "U1") (pin "52") (pinfunction "(RD)PG1_52") (pintype "bidirectional"))
    )
    (net (code "260") (name "unconnected-(U1-(RXD0{slash}PCIN8)PE0-Pad2)") (class "Default")
      (node (ref "U1") (pin "2") (pinfunction "(RXD0/PCIN8)PE0_2") (pintype "bidirectional"))
    )
    (net (code "261") (name "unconnected-(U1-(RXD1{slash}INT2)PD2-Pad45)") (class "Default")
      (node (ref "U1") (pin "45") (pinfunction "(RXD1/INT2)PD2_45") (pintype "bidirectional"))
    )
    (net (code "262") (name "unconnected-(U1-(SCK{slash}PCINT1)PB1-Pad20)") (class "Default")
      (node (ref "U1") (pin "20") (pinfunction "(SCK/PCINT1)PB1_20") (pintype "bidirectional"))
    )
    (net (code "263") (name "unconnected-(U1-(SCL{slash}INT0)PD0-Pad43)") (class "Default")
      (node (ref "U1") (pin "43") (pinfunction "(SCL/INT0)PD0_43") (pintype "bidirectional"))
    )
    (net (code "264") (name "unconnected-(U1-(SDA{slash}INT1)PD1-Pad44)") (class "Default")
      (node (ref "U1") (pin "44") (pinfunction "(SDA/INT1)PD1_44") (pintype "bidirectional"))
    )
    (net (code "265") (name "unconnected-(U1-(SS{slash}PCINT0)PB0-Pad19)") (class "Default")
      (node (ref "U1") (pin "19") (pinfunction "(SS/PCINT0)PB0_19") (pintype "bidirectional"))
    )
    (net (code "266") (name "unconnected-(U1-(T0)PD7-Pad50)") (class "Default")
      (node (ref "U1") (pin "50") (pinfunction "(T0)PD7_50") (pintype "bidirectional"))
    )
    (net (code "267") (name "unconnected-(U1-(T1)PD6-Pad49)") (class "Default")
      (node (ref "U1") (pin "49") (pinfunction "(T1)PD6_49") (pintype "bidirectional"))
    )
    (net (code "268") (name "unconnected-(U1-(T3{slash}INT6)PE6-Pad8)") (class "Default")
      (node (ref "U1") (pin "8") (pinfunction "(T3/INT6)PE6_8") (pintype "bidirectional"))
    )
    (net (code "269") (name "unconnected-(U1-(TOSC1)PG4-Pad29)") (class "Default")
      (node (ref "U1") (pin "29") (pinfunction "(TOSC1)PG4_29") (pintype "bidirectional"))
    )
    (net (code "270") (name "unconnected-(U1-(TOSC2)PG3-Pad28)") (class "Default")
      (node (ref "U1") (pin "28") (pinfunction "(TOSC2)PG3_28") (pintype "bidirectional"))
    )
    (net (code "271") (name "unconnected-(U1-(TXD0)PE1-Pad3)") (class "Default")
      (node (ref "U1") (pin "3") (pinfunction "(TXD0)PE1_3") (pintype "bidirectional"))
    )
    (net (code "272") (name "unconnected-(U1-(TXD1{slash}INT3)PD3-Pad46)") (class "Default")
      (node (ref "U1") (pin "46") (pinfunction "(TXD1/INT3)PD3_46") (pintype "bidirectional"))
    )
    (net (code "273") (name "unconnected-(U1-(WR)PG0-Pad51)") (class "Default")
      (node (ref "U1") (pin "51") (pinfunction "(WR)PG0_51") (pintype "bidirectional"))
    )
    (net (code "274") (name "unconnected-(U1-(XCK0{slash}AIN0)PE2-Pad4)") (class "Default")
      (node (ref "U1") (pin "4") (pinfunction "(XCK0/AIN0)PE2_4") (pintype "bidirectional"))
    )
    (net (code "275") (name "unconnected-(U1-(XCK1)PD5-Pad48)") (class "Default")
      (node (ref "U1") (pin "48") (pinfunction "(XCK1)PD5_48") (pintype "bidirectional"))
    )
    (net (code "276") (name "unconnected-(U1-AREF-Pad98)") (class "Default")
      (node (ref "U1") (pin "98") (pinfunction "AREF_98") (pintype "bidirectional"))
    )
    (net (code "277") (name "unconnected-(U1-PH0(RXD2)-Pad12)") (class "Default")
      (node (ref "U1") (pin "12") (pinfunction "PH0(RXD2)_12") (pintype "bidirectional"))
    )
    (net (code "278") (name "unconnected-(U1-PH1(TXD2)-Pad13)") (class "Default")
      (node (ref "U1") (pin "13") (pinfunction "PH1(TXD2)_13") (pintype "bidirectional"))
    )
    (net (code "279") (name "unconnected-(U1-PH2(XCK2)-Pad14)") (class "Default")
      (node (ref "U1") (pin "14") (pinfunction "PH2(XCK2)_14") (pintype "bidirectional"))
    )
    (net (code "280") (name "unconnected-(U1-PH3(OC4A)-Pad15)") (class "Default")
      (node (ref "U1") (pin "15") (pinfunction "PH3(OC4A)_15") (pintype "bidirectional"))
    )
    (net (code "281") (name "unconnected-(U1-PH4(OC4B)-Pad16)") (class "Default")
      (node (ref "U1") (pin "16") (pinfunction "PH4(OC4B)_16") (pintype "bidirectional"))
    )
    (net (code "282") (name "unconnected-(U1-PH5(OC4C)-Pad17)") (class "Default")
      (node (ref "U1") (pin "17") (pinfunction "PH5(OC4C)_17") (pintype "bidirectional"))
    )
    (net (code "283") (name "unconnected-(U1-PH6(OC2B)-Pad18)") (class "Default")
      (node (ref "U1") (pin "18") (pinfunction "PH6(OC2B)_18") (pintype "bidirectional"))
    )
    (net (code "284") (name "unconnected-(U1-PH7(T4)-Pad27)") (class "Default")
      (node (ref "U1") (pin "27") (pinfunction "PH7(T4)_27") (pintype "bidirectional"))
    )
    (net (code "285") (name "unconnected-(U1-PJ0(RXD3{slash}PCINT9)-Pad63)") (class "Default")
      (node (ref "U1") (pin "63") (pinfunction "PJ0(RXD3/PCINT9)_63") (pintype "bidirectional"))
    )
    (net (code "286") (name "unconnected-(U1-PJ1(TXD3{slash}PCINT10)-Pad64)") (class "Default")
      (node (ref "U1") (pin "64") (pinfunction "PJ1(TXD3/PCINT10)_64") (pintype "bidirectional"))
    )
    (net (code "287") (name "unconnected-(U1-PJ2(XCK3{slash}PCINT11)-Pad65)") (class "Default")
      (node (ref "U1") (pin "65") (pinfunction "PJ2(XCK3/PCINT11)_65") (pintype "bidirectional"))
    )
    (net (code "288") (name "unconnected-(U1-PJ3(PCINT12)-Pad66)") (class "Default")
      (node (ref "U1") (pin "66") (pinfunction "PJ3(PCINT12)_66") (pintype "bidirectional"))
    )
    (net (code "289") (name "unconnected-(U1-PJ4(PCINT13)-Pad67)") (class "Default")
      (node (ref "U1") (pin "67") (pinfunction "PJ4(PCINT13)_67") (pintype "bidirectional"))
    )
    (net (code "290") (name "unconnected-(U1-PJ5(PCINT14)-Pad68)") (class "Default")
      (node (ref "U1") (pin "68") (pinfunction "PJ5(PCINT14)_68") (pintype "bidirectional"))
    )
    (net (code "291") (name "unconnected-(U1-PJ6(PCINT15)-Pad69)") (class "Default")
      (node (ref "U1") (pin "69") (pinfunction "PJ6(PCINT15)_69") (pintype "bidirectional"))
    )
    (net (code "292") (name "unconnected-(U1-PJ7-Pad79)") (class "Default")
      (node (ref "U1") (pin "79") (pinfunction "PJ7_79") (pintype "bidirectional"))
    )
    (net (code "293") (name "unconnected-(U1-PK0(ADC8{slash}PCINT16)-Pad89)") (class "Default")
      (node (ref "U1") (pin "89") (pinfunction "PK0(ADC8/PCINT16)_89") (pintype "bidirectional"))
    )
    (net (code "294") (name "unconnected-(U1-PK1(ADC9{slash}PCINT17)-Pad88)") (class "Default")
      (node (ref "U1") (pin "88") (pinfunction "PK1(ADC9/PCINT17)_88") (pintype "bidirectional"))
    )
    (net (code "295") (name "unconnected-(U1-PK2(ADC10{slash}PCINT18)-Pad87)") (class "Default")
      (node (ref "U1") (pin "87") (pinfunction "PK2(ADC10/PCINT18)_87") (pintype "bidirectional"))
    )
    (net (code "296") (name "unconnected-(U1-PK3(ADC11{slash}PCINT19)-Pad86)") (class "Default")
      (node (ref "U1") (pin "86") (pinfunction "PK3(ADC11/PCINT19)_86") (pintype "bidirectional"))
    )
    (net (code "297") (name "unconnected-(U1-PK4(ADC12{slash}PCINT20)-Pad85)") (class "Default")
      (node (ref "U1") (pin "85") (pinfunction "PK4(ADC12/PCINT20)_85") (pintype "bidirectional"))
    )
    (net (code "298") (name "unconnected-(U1-PK5(ADC13{slash}PCINT21)-Pad84)") (class "Default")
      (node (ref "U1") (pin "84") (pinfunction "PK5(ADC13/PCINT21)_84") (pintype "bidirectional"))
    )
    (net (code "299") (name "unconnected-(U1-PK6(ADC14{slash}PCINT22)-Pad83)") (class "Default")
      (node (ref "U1") (pin "83") (pinfunction "PK6(ADC14/PCINT22)_83") (pintype "bidirectional"))
    )
    (net (code "300") (name "unconnected-(U1-PK7(ADC15{slash}PCINT23)-Pad82)") (class "Default")
      (node (ref "U1") (pin "82") (pinfunction "PK7(ADC15/PCINT23)_82") (pintype "bidirectional"))
    )
    (net (code "301") (name "unconnected-(U1-PL0(ICP4)-Pad35)") (class "Default")
      (node (ref "U1") (pin "35") (pinfunction "PL0(ICP4)_35") (pintype "bidirectional"))
    )
    (net (code "302") (name "unconnected-(U1-PL1(ICP5)-Pad36)") (class "Default")
      (node (ref "U1") (pin "36") (pinfunction "PL1(ICP5)_36") (pintype "bidirectional"))
    )
    (net (code "303") (name "unconnected-(U1-PL2(T5)-Pad37)") (class "Default")
      (node (ref "U1") (pin "37") (pinfunction "PL2(T5)_37") (pintype "bidirectional"))
    )
    (net (code "304") (name "unconnected-(U1-PL3(OC5A)-Pad38)") (class "Default")
      (node (ref "U1") (pin "38") (pinfunction "PL3(OC5A)_38") (pintype "bidirectional"))
    )
    (net (code "305") (name "unconnected-(U1-PL4(OC5B)-Pad39)") (class "Default")
      (node (ref "U1") (pin "39") (pinfunction "PL4(OC5B)_39") (pintype "bidirectional"))
    )
    (net (code "306") (name "unconnected-(U1-PL5(OC5C)-Pad40)") (class "Default")
      (node (ref "U1") (pin "40") (pinfunction "PL5(OC5C)_40") (pintype "bidirectional"))
    )
    (net (code "307") (name "unconnected-(U1-PL6-Pad41)") (class "Default")
      (node (ref "U1") (pin "41") (pinfunction "PL6_41") (pintype "bidirectional"))
    )
    (net (code "308") (name "unconnected-(U1-PL7-Pad42)") (class "Default")
      (node (ref "U1") (pin "42") (pinfunction "PL7_42") (pintype "bidirectional"))
    )
    (net (code "309") (name "unconnected-(U1-RESET-Pad30)") (class "Default")
      (node (ref "U1") (pin "30") (pinfunction "RESET_30") (pintype "input"))
    )
    (net (code "310") (name "unconnected-(U1-XTAL1-Pad34)") (class "Default")
      (node (ref "U1") (pin "34") (pinfunction "XTAL1_34") (pintype "input"))
    )
    (net (code "311") (name "unconnected-(U1-XTAL2-Pad33)") (class "Default")
      (node (ref "U1") (pin "33") (pinfunction "XTAL2_33") (pintype "output"))
    )
    (net (code "312") (name "unconnected-(U2-ADC6-Pad19)") (class "Default")
      (node (ref "U2") (pin "19") (pinfunction "ADC6_19") (pintype "bidirectional"))
    )
    (net (code "313") (name "unconnected-(U2-ADC7-Pad22)") (class "Default")
      (node (ref "U2") (pin "22") (pinfunction "ADC7_22") (pintype "bidirectional"))
    )
    (net (code "314") (name "unconnected-(U2-AGND-Pad5)") (class "Default")
      (node (ref "U2") (pin "5") (pinfunction "AGND_5") (pintype "bidirectional"))
    )
    (net (code "315") (name "unconnected-(U2-AREF-Pad20)") (class "Default")
      (node (ref "U2") (pin "20") (pinfunction "AREF_20") (pintype "bidirectional"))
    )
    (net (code "316") (name "unconnected-(U2-AVCC-Pad18)") (class "Default")
      (node (ref "U2") (pin "18") (pinfunction "AVCC_18") (pintype "bidirectional"))
    )
    (net (code "317") (name "unconnected-(U2-GND-Pad3)") (class "Default")
      (node (ref "U2") (pin "3") (pinfunction "GND_3") (pintype "bidirectional"))
    )
    (net (code "318") (name "unconnected-(U2-GND-Pad21)") (class "Default")
      (node (ref "U2") (pin "21") (pinfunction "GND_21") (pintype "bidirectional"))
    )
    (net (code "319") (name "unconnected-(U2-PB0(ICP)-Pad12)") (class "Default")
      (node (ref "U2") (pin "12") (pinfunction "PB0(ICP)_12") (pintype "bidirectional"))
    )
    (net (code "320") (name "unconnected-(U2-PB1(OC1A)-Pad13)") (class "Default")
      (node (ref "U2") (pin "13") (pinfunction "PB1(OC1A)_13") (pintype "bidirectional"))
    )
    (net (code "321") (name "unconnected-(U2-PB2(SS{slash}OC1B)-Pad14)") (class "Default")
      (node (ref "U2") (pin "14") (pinfunction "PB2(SS/OC1B)_14") (pintype "bidirectional"))
    )
    (net (code "322") (name "unconnected-(U2-PB3(MOSI{slash}OC2)-Pad15)") (class "Default")
      (node (ref "U2") (pin "15") (pinfunction "PB3(MOSI/OC2)_15") (pintype "bidirectional"))
    )
    (net (code "323") (name "unconnected-(U2-PB4(MISO)-Pad16)") (class "Default")
      (node (ref "U2") (pin "16") (pinfunction "PB4(MISO)_16") (pintype "bidirectional"))
    )
    (net (code "324") (name "unconnected-(U2-PB5(SCK)-Pad17)") (class "Default")
      (node (ref "U2") (pin "17") (pinfunction "PB5(SCK)_17") (pintype "bidirectional"))
    )
    (net (code "325") (name "unconnected-(U2-PB6(XTAL1{slash}TOSC1)-Pad7)") (class "Default")
      (node (ref "U2") (pin "7") (pinfunction "PB6(XTAL1/TOSC1)_7") (pintype "bidirectional"))
    )
    (net (code "326") (name "unconnected-(U2-PB7(XTAL2{slash}TOSC2)-Pad8)") (class "Default")
      (node (ref "U2") (pin "8") (pinfunction "PB7(XTAL2/TOSC2)_8") (pintype "bidirectional"))
    )
    (net (code "327") (name "unconnected-(U2-PC0(ADC0)-Pad23)") (class "Default")
      (node (ref "U2") (pin "23") (pinfunction "PC0(ADC0)_23") (pintype "bidirectional"))
    )
    (net (code "328") (name "unconnected-(U2-PC1(ADC1)-Pad24)") (class "Default")
      (node (ref "U2") (pin "24") (pinfunction "PC1(ADC1)_24") (pintype "bidirectional"))
    )
    (net (code "329") (name "unconnected-(U2-PC2(ADC2)-Pad25)") (class "Default")
      (node (ref "U2") (pin "25") (pinfunction "PC2(ADC2)_25") (pintype "bidirectional"))
    )
    (net (code "330") (name "unconnected-(U2-PC3(ADC3)-Pad26)") (class "Default")
      (node (ref "U2") (pin "26") (pinfunction "PC3(ADC3)_26") (pintype "bidirectional"))
    )
    (net (code "331") (name "unconnected-(U2-PC4(ADC4{slash}SDA)-Pad27)") (class "Default")
      (node (ref "U2") (pin "27") (pinfunction "PC4(ADC4/SDA)_27") (pintype "bidirectional"))
    )
    (net (code "332") (name "unconnected-(U2-PC5(ADC5{slash}SCL)-Pad28)") (class "Default")
      (node (ref "U2") (pin "28") (pinfunction "PC5(ADC5/SCL)_28") (pintype "bidirectional"))
    )
    (net (code "333") (name "unconnected-(U2-PC6({slash}RESET)-Pad29)") (class "Default")
      (node (ref "U2") (pin "29") (pinfunction "PC6(/RESET)_29") (pintype "bidirectional"))
    )
    (net (code "334") (name "unconnected-(U2-PD0(RXD)-Pad30)") (class "Default")
      (node (ref "U2") (pin "30") (pinfunction "PD0(RXD)_30") (pintype "bidirectional"))
    )
    (net (code "335") (name "unconnected-(U2-PD1(TXD)-Pad31)") (class "Default")
      (node (ref "U2") (pin "31") (pinfunction "PD1(TXD)_31") (pintype "bidirectional"))
    )
    (net (code "336") (name "unconnected-(U2-PD2(INT0)-Pad32)") (class "Default")
      (node (ref "U2") (pin "32") (pinfunction "PD2(INT0)_32") (pintype "bidirectional"))
    )
    (net (code "337") (name "unconnected-(U2-PD3(INT1)-Pad1)") (class "Default")
      (node (ref "U2") (pin "1") (pinfunction "PD3(INT1)_1") (pintype "bidirectional"))
    )
    (net (code "338") (name "unconnected-(U2-PD4(XCK{slash}T0)-Pad2)") (class "Default")
      (node (ref "U2") (pin "2") (pinfunction "PD4(XCK/T0)_2") (pintype "bidirectional"))
    )
    (net (code "339") (name "unconnected-(U2-PD5(T1)-Pad9)") (class "Default")
      (node (ref "U2") (pin "9") (pinfunction "PD5(T1)_9") (pintype "bidirectional"))
    )
    (net (code "340") (name "unconnected-(U2-PD6(AIN0)-Pad10)") (class "Default")
      (node (ref "U2") (pin "10") (pinfunction "PD6(AIN0)_10") (pintype "bidirectional"))
    )
    (net (code "341") (name "unconnected-(U2-PD7(AIN1)-Pad11)") (class "Default")
      (node (ref "U2") (pin "11") (pinfunction "PD7(AIN1)_11") (pintype "bidirectional"))
    )
    (net (code "342") (name "unconnected-(U2-VCC-Pad4)") (class "Default")
      (node (ref "U2") (pin "4") (pinfunction "VCC_4") (pintype "bidirectional"))
    )
    (net (code "343") (name "unconnected-(U2-VCC-Pad6)") (class "Default")
      (node (ref "U2") (pin "6") (pinfunction "VCC_6") (pintype "bidirectional"))
    )
  )
)
